# FLAT_LED.net
KiCad netlist of a schematic drawn in Altium Designer
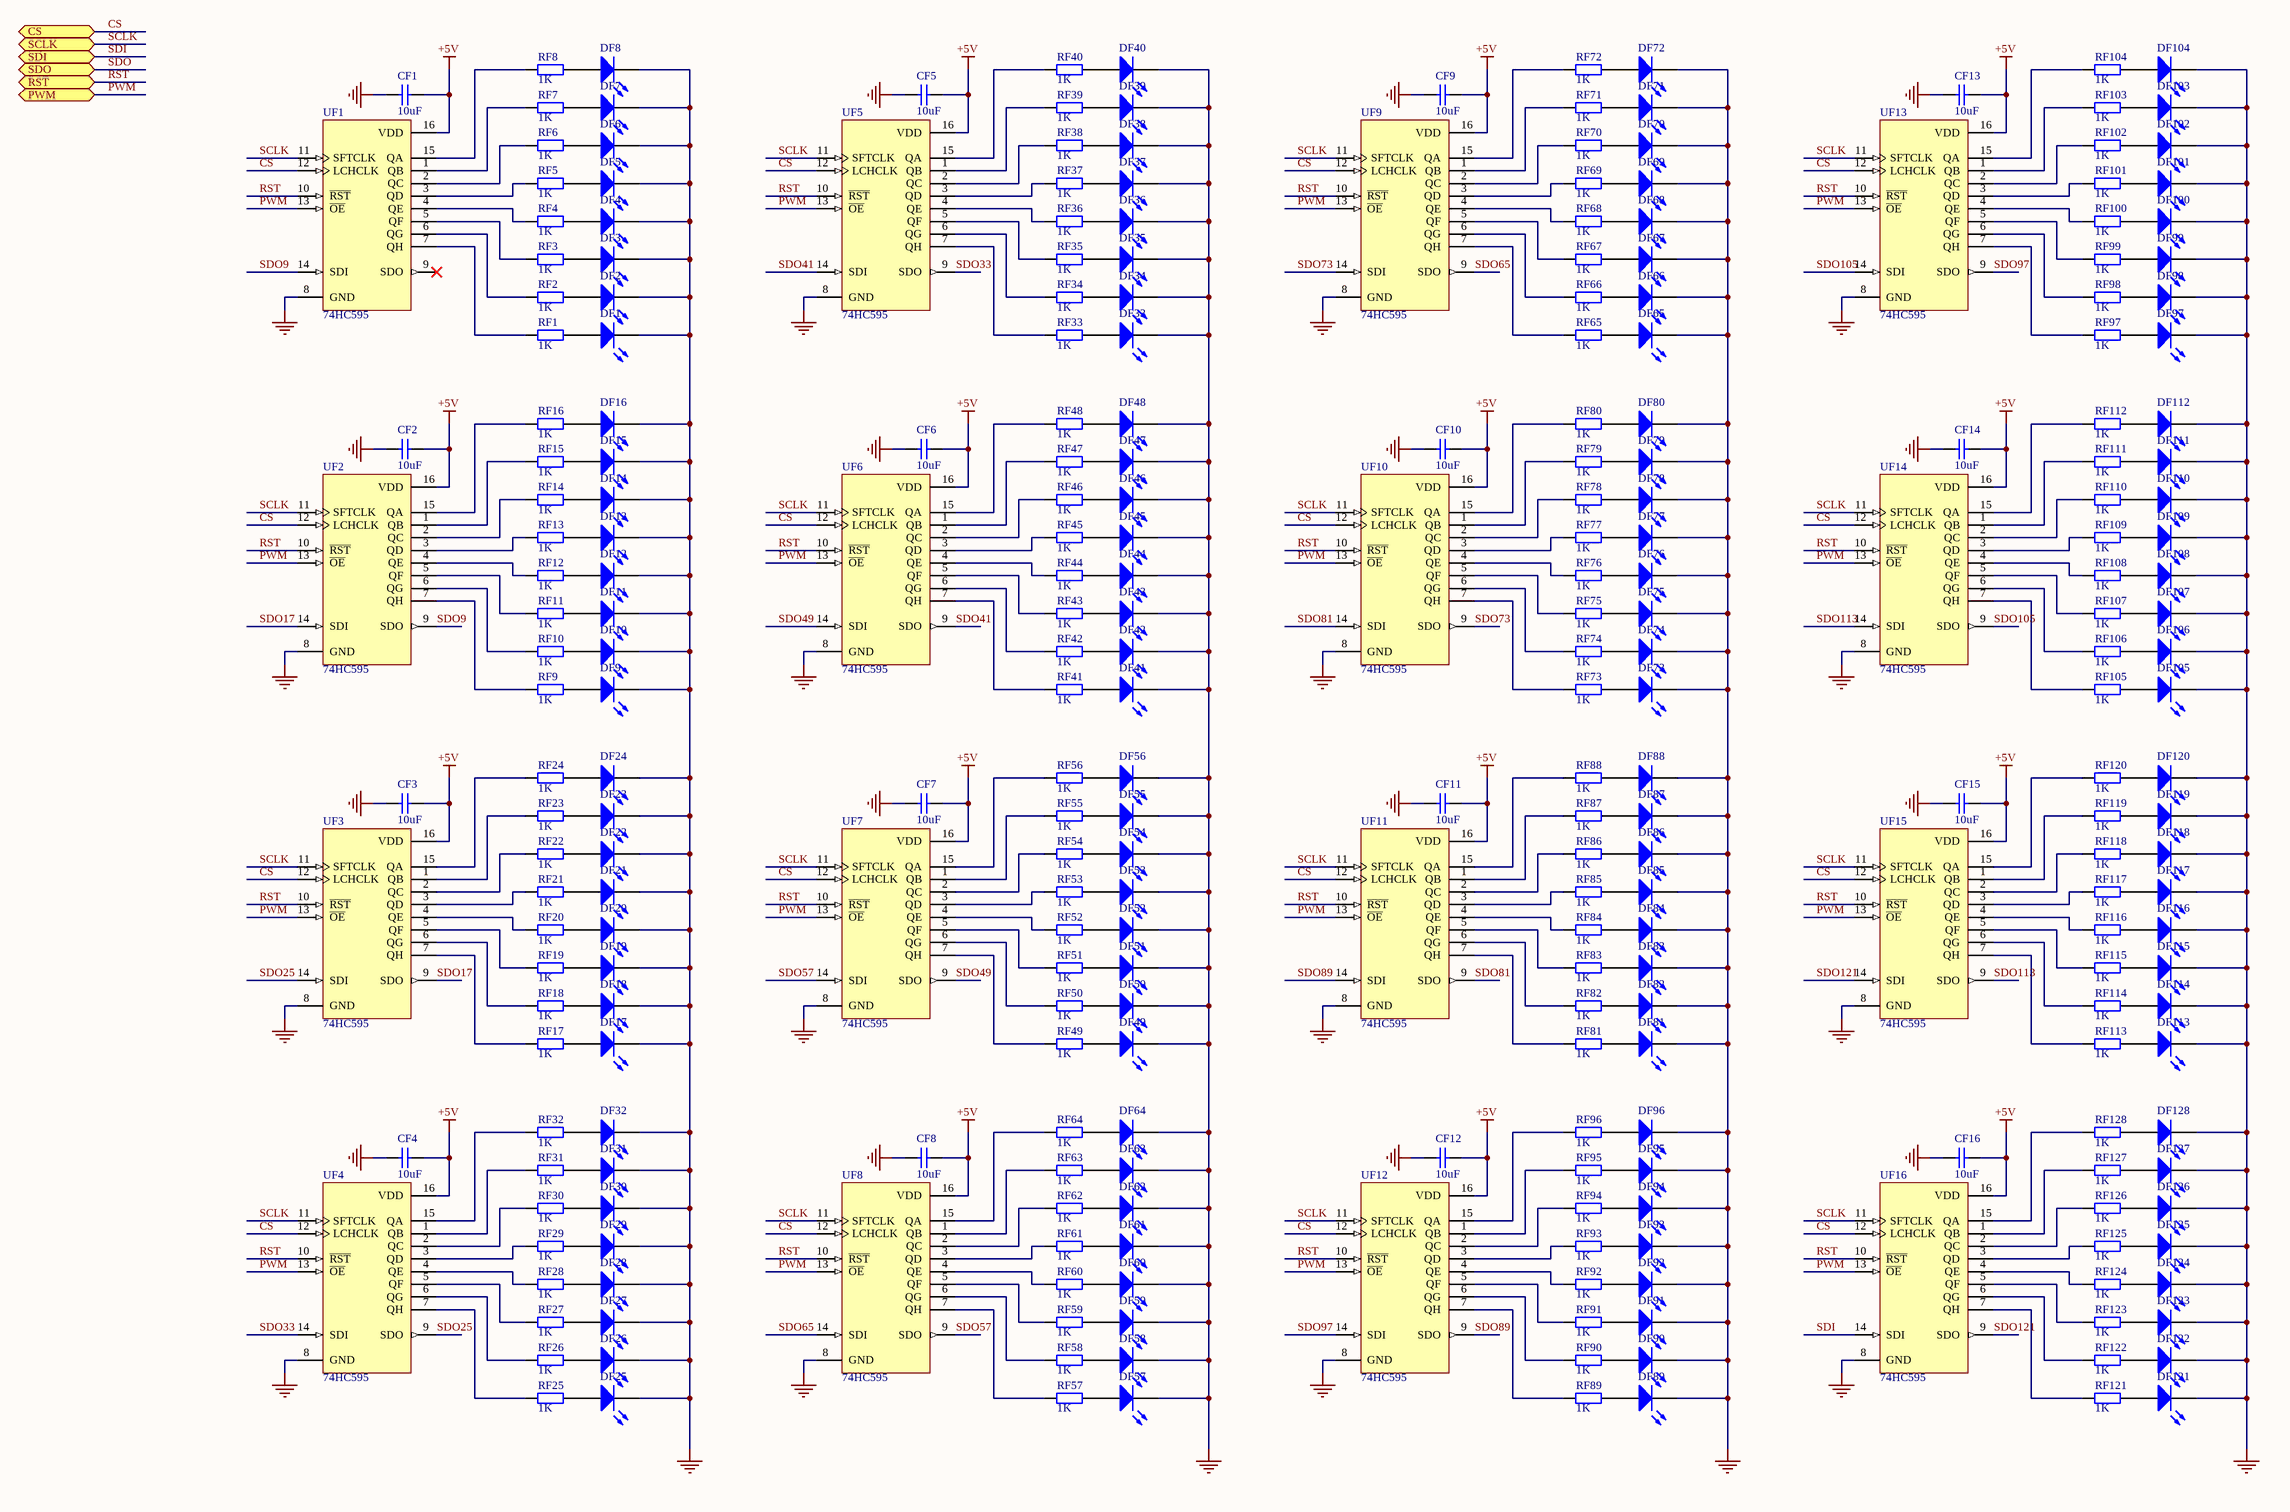
[diagram p0: FLAT_LED.SchDoc]

(export (version "E")
  (design (tool "Eeschema 10.0.6"))
  (components
    (comp (ref "CF1")
      (value "10uF")
      (footprint "CAPC1608N")
      (description "Capacitor")
      (fields (field (name "Comment") "Cap1") (field (name "PUBLISHER") "Altium Limited"))
      (libsource (lib "Peace的集成库") (part "Cap1"))
    )
    (comp (ref "CF2")
      (value "10uF")
      (footprint "CAPC1608N")
      (description "Capacitor")
      (fields (field (name "Comment") "Cap1") (field (name "PUBLISHER") "Altium Limited"))
      (libsource (lib "Peace的集成库") (part "Cap1"))
    )
    (comp (ref "CF3")
      (value "10uF")
      (footprint "CAPC1608N")
      (description "Capacitor")
      (fields (field (name "Comment") "Cap1") (field (name "PUBLISHER") "Altium Limited"))
      (libsource (lib "Peace的集成库") (part "Cap1"))
    )
    (comp (ref "CF4")
      (value "10uF")
      (footprint "CAPC1608N")
      (description "Capacitor")
      (fields (field (name "Comment") "Cap1") (field (name "PUBLISHER") "Altium Limited"))
      (libsource (lib "Peace的集成库") (part "Cap1"))
    )
    (comp (ref "CF5")
      (value "10uF")
      (footprint "CAPC1608N")
      (description "Capacitor")
      (fields (field (name "Comment") "Cap1") (field (name "PUBLISHER") "Altium Limited"))
      (libsource (lib "Peace的集成库") (part "Cap1"))
    )
    (comp (ref "CF6")
      (value "10uF")
      (footprint "CAPC1608N")
      (description "Capacitor")
      (fields (field (name "Comment") "Cap1") (field (name "PUBLISHER") "Altium Limited"))
      (libsource (lib "Peace的集成库") (part "Cap1"))
    )
    (comp (ref "CF7")
      (value "10uF")
      (footprint "CAPC1608N")
      (description "Capacitor")
      (fields (field (name "Comment") "Cap1") (field (name "PUBLISHER") "Altium Limited"))
      (libsource (lib "Peace的集成库") (part "Cap1"))
    )
    (comp (ref "CF8")
      (value "10uF")
      (footprint "CAPC1608N")
      (description "Capacitor")
      (fields (field (name "Comment") "Cap1") (field (name "PUBLISHER") "Altium Limited"))
      (libsource (lib "Peace的集成库") (part "Cap1"))
    )
    (comp (ref "CF9")
      (value "10uF")
      (footprint "CAPC1608N")
      (description "Capacitor")
      (fields (field (name "Comment") "Cap1") (field (name "PUBLISHER") "Altium Limited"))
      (libsource (lib "Peace的集成库") (part "Cap1"))
    )
    (comp (ref "CF10")
      (value "10uF")
      (footprint "CAPC1608N")
      (description "Capacitor")
      (fields (field (name "Comment") "Cap1") (field (name "PUBLISHER") "Altium Limited"))
      (libsource (lib "Peace的集成库") (part "Cap1"))
    )
    (comp (ref "CF11")
      (value "10uF")
      (footprint "CAPC1608N")
      (description "Capacitor")
      (fields (field (name "Comment") "Cap1") (field (name "PUBLISHER") "Altium Limited"))
      (libsource (lib "Peace的集成库") (part "Cap1"))
    )
    (comp (ref "CF12")
      (value "10uF")
      (footprint "CAPC1608N")
      (description "Capacitor")
      (fields (field (name "Comment") "Cap1") (field (name "PUBLISHER") "Altium Limited"))
      (libsource (lib "Peace的集成库") (part "Cap1"))
    )
    (comp (ref "CF13")
      (value "10uF")
      (footprint "CAPC1608N")
      (description "Capacitor")
      (fields (field (name "Comment") "Cap1") (field (name "PUBLISHER") "Altium Limited"))
      (libsource (lib "Peace的集成库") (part "Cap1"))
    )
    (comp (ref "CF14")
      (value "10uF")
      (footprint "CAPC1608N")
      (description "Capacitor")
      (fields (field (name "Comment") "Cap1") (field (name "PUBLISHER") "Altium Limited"))
      (libsource (lib "Peace的集成库") (part "Cap1"))
    )
    (comp (ref "CF15")
      (value "10uF")
      (footprint "CAPC1608N")
      (description "Capacitor")
      (fields (field (name "Comment") "Cap1") (field (name "PUBLISHER") "Altium Limited"))
      (libsource (lib "Peace的集成库") (part "Cap1"))
    )
    (comp (ref "CF16")
      (value "10uF")
      (footprint "CAPC1608N")
      (description "Capacitor")
      (fields (field (name "Comment") "Cap1") (field (name "PUBLISHER") "Altium Limited"))
      (libsource (lib "Peace的集成库") (part "Cap1"))
    )
    (comp (ref "DF1")
      (value "~")
      (footprint "CD1005-0402-L")
      (description "Typical RED, GREEN, YELLOW, AMBER GaAs LED")
      (fields (field (name "PUBLISHER") "Altium Limited"))
      (libsource (lib "Peace的集成库") (part "LED2"))
    )
    (comp (ref "DF2")
      (value "~")
      (footprint "CD1005-0402-L")
      (description "Typical RED, GREEN, YELLOW, AMBER GaAs LED")
      (fields (field (name "PUBLISHER") "Altium Limited"))
      (libsource (lib "Peace的集成库") (part "LED2"))
    )
    (comp (ref "DF3")
      (value "~")
      (footprint "CD1005-0402-L")
      (description "Typical RED, GREEN, YELLOW, AMBER GaAs LED")
      (fields (field (name "PUBLISHER") "Altium Limited"))
      (libsource (lib "Peace的集成库") (part "LED2"))
    )
    (comp (ref "DF4")
      (value "~")
      (footprint "CD1005-0402-L")
      (description "Typical RED, GREEN, YELLOW, AMBER GaAs LED")
      (fields (field (name "PUBLISHER") "Altium Limited"))
      (libsource (lib "Peace的集成库") (part "LED2"))
    )
    (comp (ref "DF5")
      (value "~")
      (footprint "CD1005-0402-L")
      (description "Typical RED, GREEN, YELLOW, AMBER GaAs LED")
      (fields (field (name "PUBLISHER") "Altium Limited"))
      (libsource (lib "Peace的集成库") (part "LED2"))
    )
    (comp (ref "DF6")
      (value "~")
      (footprint "CD1005-0402-L")
      (description "Typical RED, GREEN, YELLOW, AMBER GaAs LED")
      (fields (field (name "PUBLISHER") "Altium Limited"))
      (libsource (lib "Peace的集成库") (part "LED2"))
    )
    (comp (ref "DF7")
      (value "~")
      (footprint "CD1005-0402-L")
      (description "Typical RED, GREEN, YELLOW, AMBER GaAs LED")
      (fields (field (name "PUBLISHER") "Altium Limited"))
      (libsource (lib "Peace的集成库") (part "LED2"))
    )
    (comp (ref "DF8")
      (value "~")
      (footprint "CD1005-0402-L")
      (description "Typical RED, GREEN, YELLOW, AMBER GaAs LED")
      (fields (field (name "PUBLISHER") "Altium Limited"))
      (libsource (lib "Peace的集成库") (part "LED2"))
    )
    (comp (ref "DF9")
      (value "~")
      (footprint "CD1005-0402-L")
      (description "Typical RED, GREEN, YELLOW, AMBER GaAs LED")
      (fields (field (name "PUBLISHER") "Altium Limited"))
      (libsource (lib "Peace的集成库") (part "LED2"))
    )
    (comp (ref "DF10")
      (value "~")
      (footprint "CD1005-0402-L")
      (description "Typical RED, GREEN, YELLOW, AMBER GaAs LED")
      (fields (field (name "PUBLISHER") "Altium Limited"))
      (libsource (lib "Peace的集成库") (part "LED2"))
    )
    (comp (ref "DF11")
      (value "~")
      (footprint "CD1005-0402-L")
      (description "Typical RED, GREEN, YELLOW, AMBER GaAs LED")
      (fields (field (name "PUBLISHER") "Altium Limited"))
      (libsource (lib "Peace的集成库") (part "LED2"))
    )
    (comp (ref "DF12")
      (value "~")
      (footprint "CD1005-0402-L")
      (description "Typical RED, GREEN, YELLOW, AMBER GaAs LED")
      (fields (field (name "PUBLISHER") "Altium Limited"))
      (libsource (lib "Peace的集成库") (part "LED2"))
    )
    (comp (ref "DF13")
      (value "~")
      (footprint "CD1005-0402-L")
      (description "Typical RED, GREEN, YELLOW, AMBER GaAs LED")
      (fields (field (name "PUBLISHER") "Altium Limited"))
      (libsource (lib "Peace的集成库") (part "LED2"))
    )
    (comp (ref "DF14")
      (value "~")
      (footprint "CD1005-0402-L")
      (description "Typical RED, GREEN, YELLOW, AMBER GaAs LED")
      (fields (field (name "PUBLISHER") "Altium Limited"))
      (libsource (lib "Peace的集成库") (part "LED2"))
    )
    (comp (ref "DF15")
      (value "~")
      (footprint "CD1005-0402-L")
      (description "Typical RED, GREEN, YELLOW, AMBER GaAs LED")
      (fields (field (name "PUBLISHER") "Altium Limited"))
      (libsource (lib "Peace的集成库") (part "LED2"))
    )
    (comp (ref "DF16")
      (value "~")
      (footprint "CD1005-0402-L")
      (description "Typical RED, GREEN, YELLOW, AMBER GaAs LED")
      (fields (field (name "PUBLISHER") "Altium Limited"))
      (libsource (lib "Peace的集成库") (part "LED2"))
    )
    (comp (ref "DF17")
      (value "~")
      (footprint "CD1005-0402-L")
      (description "Typical RED, GREEN, YELLOW, AMBER GaAs LED")
      (fields (field (name "PUBLISHER") "Altium Limited"))
      (libsource (lib "Peace的集成库") (part "LED2"))
    )
    (comp (ref "DF18")
      (value "~")
      (footprint "CD1005-0402-L")
      (description "Typical RED, GREEN, YELLOW, AMBER GaAs LED")
      (fields (field (name "PUBLISHER") "Altium Limited"))
      (libsource (lib "Peace的集成库") (part "LED2"))
    )
    (comp (ref "DF19")
      (value "~")
      (footprint "CD1005-0402-L")
      (description "Typical RED, GREEN, YELLOW, AMBER GaAs LED")
      (fields (field (name "PUBLISHER") "Altium Limited"))
      (libsource (lib "Peace的集成库") (part "LED2"))
    )
    (comp (ref "DF20")
      (value "~")
      (footprint "CD1005-0402-L")
      (description "Typical RED, GREEN, YELLOW, AMBER GaAs LED")
      (fields (field (name "PUBLISHER") "Altium Limited"))
      (libsource (lib "Peace的集成库") (part "LED2"))
    )
    (comp (ref "DF21")
      (value "~")
      (footprint "CD1005-0402-L")
      (description "Typical RED, GREEN, YELLOW, AMBER GaAs LED")
      (fields (field (name "PUBLISHER") "Altium Limited"))
      (libsource (lib "Peace的集成库") (part "LED2"))
    )
    (comp (ref "DF22")
      (value "~")
      (footprint "CD1005-0402-L")
      (description "Typical RED, GREEN, YELLOW, AMBER GaAs LED")
      (fields (field (name "PUBLISHER") "Altium Limited"))
      (libsource (lib "Peace的集成库") (part "LED2"))
    )
    (comp (ref "DF23")
      (value "~")
      (footprint "CD1005-0402-L")
      (description "Typical RED, GREEN, YELLOW, AMBER GaAs LED")
      (fields (field (name "PUBLISHER") "Altium Limited"))
      (libsource (lib "Peace的集成库") (part "LED2"))
    )
    (comp (ref "DF24")
      (value "~")
      (footprint "CD1005-0402-L")
      (description "Typical RED, GREEN, YELLOW, AMBER GaAs LED")
      (fields (field (name "PUBLISHER") "Altium Limited"))
      (libsource (lib "Peace的集成库") (part "LED2"))
    )
    (comp (ref "DF25")
      (value "~")
      (footprint "CD1005-0402-L")
      (description "Typical RED, GREEN, YELLOW, AMBER GaAs LED")
      (fields (field (name "PUBLISHER") "Altium Limited"))
      (libsource (lib "Peace的集成库") (part "LED2"))
    )
    (comp (ref "DF26")
      (value "~")
      (footprint "CD1005-0402-L")
      (description "Typical RED, GREEN, YELLOW, AMBER GaAs LED")
      (fields (field (name "PUBLISHER") "Altium Limited"))
      (libsource (lib "Peace的集成库") (part "LED2"))
    )
    (comp (ref "DF27")
      (value "~")
      (footprint "CD1005-0402-L")
      (description "Typical RED, GREEN, YELLOW, AMBER GaAs LED")
      (fields (field (name "PUBLISHER") "Altium Limited"))
      (libsource (lib "Peace的集成库") (part "LED2"))
    )
    (comp (ref "DF28")
      (value "~")
      (footprint "CD1005-0402-L")
      (description "Typical RED, GREEN, YELLOW, AMBER GaAs LED")
      (fields (field (name "PUBLISHER") "Altium Limited"))
      (libsource (lib "Peace的集成库") (part "LED2"))
    )
    (comp (ref "DF29")
      (value "~")
      (footprint "CD1005-0402-L")
      (description "Typical RED, GREEN, YELLOW, AMBER GaAs LED")
      (fields (field (name "PUBLISHER") "Altium Limited"))
      (libsource (lib "Peace的集成库") (part "LED2"))
    )
    (comp (ref "DF30")
      (value "~")
      (footprint "CD1005-0402-L")
      (description "Typical RED, GREEN, YELLOW, AMBER GaAs LED")
      (fields (field (name "PUBLISHER") "Altium Limited"))
      (libsource (lib "Peace的集成库") (part "LED2"))
    )
    (comp (ref "DF31")
      (value "~")
      (footprint "CD1005-0402-L")
      (description "Typical RED, GREEN, YELLOW, AMBER GaAs LED")
      (fields (field (name "PUBLISHER") "Altium Limited"))
      (libsource (lib "Peace的集成库") (part "LED2"))
    )
    (comp (ref "DF32")
      (value "~")
      (footprint "CD1005-0402-L")
      (description "Typical RED, GREEN, YELLOW, AMBER GaAs LED")
      (fields (field (name "PUBLISHER") "Altium Limited"))
      (libsource (lib "Peace的集成库") (part "LED2"))
    )
    (comp (ref "DF33")
      (value "~")
      (footprint "CD1005-0402-L")
      (description "Typical RED, GREEN, YELLOW, AMBER GaAs LED")
      (fields (field (name "PUBLISHER") "Altium Limited"))
      (libsource (lib "Peace的集成库") (part "LED2"))
    )
    (comp (ref "DF34")
      (value "~")
      (footprint "CD1005-0402-L")
      (description "Typical RED, GREEN, YELLOW, AMBER GaAs LED")
      (fields (field (name "PUBLISHER") "Altium Limited"))
      (libsource (lib "Peace的集成库") (part "LED2"))
    )
    (comp (ref "DF35")
      (value "~")
      (footprint "CD1005-0402-L")
      (description "Typical RED, GREEN, YELLOW, AMBER GaAs LED")
      (fields (field (name "PUBLISHER") "Altium Limited"))
      (libsource (lib "Peace的集成库") (part "LED2"))
    )
    (comp (ref "DF36")
      (value "~")
      (footprint "CD1005-0402-L")
      (description "Typical RED, GREEN, YELLOW, AMBER GaAs LED")
      (fields (field (name "PUBLISHER") "Altium Limited"))
      (libsource (lib "Peace的集成库") (part "LED2"))
    )
    (comp (ref "DF37")
      (value "~")
      (footprint "CD1005-0402-L")
      (description "Typical RED, GREEN, YELLOW, AMBER GaAs LED")
      (fields (field (name "PUBLISHER") "Altium Limited"))
      (libsource (lib "Peace的集成库") (part "LED2"))
    )
    (comp (ref "DF38")
      (value "~")
      (footprint "CD1005-0402-L")
      (description "Typical RED, GREEN, YELLOW, AMBER GaAs LED")
      (fields (field (name "PUBLISHER") "Altium Limited"))
      (libsource (lib "Peace的集成库") (part "LED2"))
    )
    (comp (ref "DF39")
      (value "~")
      (footprint "CD1005-0402-L")
      (description "Typical RED, GREEN, YELLOW, AMBER GaAs LED")
      (fields (field (name "PUBLISHER") "Altium Limited"))
      (libsource (lib "Peace的集成库") (part "LED2"))
    )
    (comp (ref "DF40")
      (value "~")
      (footprint "CD1005-0402-L")
      (description "Typical RED, GREEN, YELLOW, AMBER GaAs LED")
      (fields (field (name "PUBLISHER") "Altium Limited"))
      (libsource (lib "Peace的集成库") (part "LED2"))
    )
    (comp (ref "DF41")
      (value "~")
      (footprint "CD1005-0402-L")
      (description "Typical RED, GREEN, YELLOW, AMBER GaAs LED")
      (fields (field (name "PUBLISHER") "Altium Limited"))
      (libsource (lib "Peace的集成库") (part "LED2"))
    )
    (comp (ref "DF42")
      (value "~")
      (footprint "CD1005-0402-L")
      (description "Typical RED, GREEN, YELLOW, AMBER GaAs LED")
      (fields (field (name "PUBLISHER") "Altium Limited"))
      (libsource (lib "Peace的集成库") (part "LED2"))
    )
    (comp (ref "DF43")
      (value "~")
      (footprint "CD1005-0402-L")
      (description "Typical RED, GREEN, YELLOW, AMBER GaAs LED")
      (fields (field (name "PUBLISHER") "Altium Limited"))
      (libsource (lib "Peace的集成库") (part "LED2"))
    )
    (comp (ref "DF44")
      (value "~")
      (footprint "CD1005-0402-L")
      (description "Typical RED, GREEN, YELLOW, AMBER GaAs LED")
      (fields (field (name "PUBLISHER") "Altium Limited"))
      (libsource (lib "Peace的集成库") (part "LED2"))
    )
    (comp (ref "DF45")
      (value "~")
      (footprint "CD1005-0402-L")
      (description "Typical RED, GREEN, YELLOW, AMBER GaAs LED")
      (fields (field (name "PUBLISHER") "Altium Limited"))
      (libsource (lib "Peace的集成库") (part "LED2"))
    )
    (comp (ref "DF46")
      (value "~")
      (footprint "CD1005-0402-L")
      (description "Typical RED, GREEN, YELLOW, AMBER GaAs LED")
      (fields (field (name "PUBLISHER") "Altium Limited"))
      (libsource (lib "Peace的集成库") (part "LED2"))
    )
    (comp (ref "DF47")
      (value "~")
      (footprint "CD1005-0402-L")
      (description "Typical RED, GREEN, YELLOW, AMBER GaAs LED")
      (fields (field (name "PUBLISHER") "Altium Limited"))
      (libsource (lib "Peace的集成库") (part "LED2"))
    )
    (comp (ref "DF48")
      (value "~")
      (footprint "CD1005-0402-L")
      (description "Typical RED, GREEN, YELLOW, AMBER GaAs LED")
      (fields (field (name "PUBLISHER") "Altium Limited"))
      (libsource (lib "Peace的集成库") (part "LED2"))
    )
    (comp (ref "DF49")
      (value "~")
      (footprint "CD1005-0402-L")
      (description "Typical RED, GREEN, YELLOW, AMBER GaAs LED")
      (fields (field (name "PUBLISHER") "Altium Limited"))
      (libsource (lib "Peace的集成库") (part "LED2"))
    )
    (comp (ref "DF50")
      (value "~")
      (footprint "CD1005-0402-L")
      (description "Typical RED, GREEN, YELLOW, AMBER GaAs LED")
      (fields (field (name "PUBLISHER") "Altium Limited"))
      (libsource (lib "Peace的集成库") (part "LED2"))
    )
    (comp (ref "DF51")
      (value "~")
      (footprint "CD1005-0402-L")
      (description "Typical RED, GREEN, YELLOW, AMBER GaAs LED")
      (fields (field (name "PUBLISHER") "Altium Limited"))
      (libsource (lib "Peace的集成库") (part "LED2"))
    )
    (comp (ref "DF52")
      (value "~")
      (footprint "CD1005-0402-L")
      (description "Typical RED, GREEN, YELLOW, AMBER GaAs LED")
      (fields (field (name "PUBLISHER") "Altium Limited"))
      (libsource (lib "Peace的集成库") (part "LED2"))
    )
    (comp (ref "DF53")
      (value "~")
      (footprint "CD1005-0402-L")
      (description "Typical RED, GREEN, YELLOW, AMBER GaAs LED")
      (fields (field (name "PUBLISHER") "Altium Limited"))
      (libsource (lib "Peace的集成库") (part "LED2"))
    )
    (comp (ref "DF54")
      (value "~")
      (footprint "CD1005-0402-L")
      (description "Typical RED, GREEN, YELLOW, AMBER GaAs LED")
      (fields (field (name "PUBLISHER") "Altium Limited"))
      (libsource (lib "Peace的集成库") (part "LED2"))
    )
    (comp (ref "DF55")
      (value "~")
      (footprint "CD1005-0402-L")
      (description "Typical RED, GREEN, YELLOW, AMBER GaAs LED")
      (fields (field (name "PUBLISHER") "Altium Limited"))
      (libsource (lib "Peace的集成库") (part "LED2"))
    )
    (comp (ref "DF56")
      (value "~")
      (footprint "CD1005-0402-L")
      (description "Typical RED, GREEN, YELLOW, AMBER GaAs LED")
      (fields (field (name "PUBLISHER") "Altium Limited"))
      (libsource (lib "Peace的集成库") (part "LED2"))
    )
    (comp (ref "DF57")
      (value "~")
      (footprint "CD1005-0402-L")
      (description "Typical RED, GREEN, YELLOW, AMBER GaAs LED")
      (fields (field (name "PUBLISHER") "Altium Limited"))
      (libsource (lib "Peace的集成库") (part "LED2"))
    )
    (comp (ref "DF58")
      (value "~")
      (footprint "CD1005-0402-L")
      (description "Typical RED, GREEN, YELLOW, AMBER GaAs LED")
      (fields (field (name "PUBLISHER") "Altium Limited"))
      (libsource (lib "Peace的集成库") (part "LED2"))
    )
    (comp (ref "DF59")
      (value "~")
      (footprint "CD1005-0402-L")
      (description "Typical RED, GREEN, YELLOW, AMBER GaAs LED")
      (fields (field (name "PUBLISHER") "Altium Limited"))
      (libsource (lib "Peace的集成库") (part "LED2"))
    )
    (comp (ref "DF60")
      (value "~")
      (footprint "CD1005-0402-L")
      (description "Typical RED, GREEN, YELLOW, AMBER GaAs LED")
      (fields (field (name "PUBLISHER") "Altium Limited"))
      (libsource (lib "Peace的集成库") (part "LED2"))
    )
    (comp (ref "DF61")
      (value "~")
      (footprint "CD1005-0402-L")
      (description "Typical RED, GREEN, YELLOW, AMBER GaAs LED")
      (fields (field (name "PUBLISHER") "Altium Limited"))
      (libsource (lib "Peace的集成库") (part "LED2"))
    )
    (comp (ref "DF62")
      (value "~")
      (footprint "CD1005-0402-L")
      (description "Typical RED, GREEN, YELLOW, AMBER GaAs LED")
      (fields (field (name "PUBLISHER") "Altium Limited"))
      (libsource (lib "Peace的集成库") (part "LED2"))
    )
    (comp (ref "DF63")
      (value "~")
      (footprint "CD1005-0402-L")
      (description "Typical RED, GREEN, YELLOW, AMBER GaAs LED")
      (fields (field (name "PUBLISHER") "Altium Limited"))
      (libsource (lib "Peace的集成库") (part "LED2"))
    )
    (comp (ref "DF64")
      (value "~")
      (footprint "CD1005-0402-L")
      (description "Typical RED, GREEN, YELLOW, AMBER GaAs LED")
      (fields (field (name "PUBLISHER") "Altium Limited"))
      (libsource (lib "Peace的集成库") (part "LED2"))
    )
    (comp (ref "DF65")
      (value "~")
      (footprint "CD1005-0402-L")
      (description "Typical RED, GREEN, YELLOW, AMBER GaAs LED")
      (fields (field (name "PUBLISHER") "Altium Limited"))
      (libsource (lib "Peace的集成库") (part "LED2"))
    )
    (comp (ref "DF66")
      (value "~")
      (footprint "CD1005-0402-L")
      (description "Typical RED, GREEN, YELLOW, AMBER GaAs LED")
      (fields (field (name "PUBLISHER") "Altium Limited"))
      (libsource (lib "Peace的集成库") (part "LED2"))
    )
    (comp (ref "DF67")
      (value "~")
      (footprint "CD1005-0402-L")
      (description "Typical RED, GREEN, YELLOW, AMBER GaAs LED")
      (fields (field (name "PUBLISHER") "Altium Limited"))
      (libsource (lib "Peace的集成库") (part "LED2"))
    )
    (comp (ref "DF68")
      (value "~")
      (footprint "CD1005-0402-L")
      (description "Typical RED, GREEN, YELLOW, AMBER GaAs LED")
      (fields (field (name "PUBLISHER") "Altium Limited"))
      (libsource (lib "Peace的集成库") (part "LED2"))
    )
    (comp (ref "DF69")
      (value "~")
      (footprint "CD1005-0402-L")
      (description "Typical RED, GREEN, YELLOW, AMBER GaAs LED")
      (fields (field (name "PUBLISHER") "Altium Limited"))
      (libsource (lib "Peace的集成库") (part "LED2"))
    )
    (comp (ref "DF70")
      (value "~")
      (footprint "CD1005-0402-L")
      (description "Typical RED, GREEN, YELLOW, AMBER GaAs LED")
      (fields (field (name "PUBLISHER") "Altium Limited"))
      (libsource (lib "Peace的集成库") (part "LED2"))
    )
    (comp (ref "DF71")
      (value "~")
      (footprint "CD1005-0402-L")
      (description "Typical RED, GREEN, YELLOW, AMBER GaAs LED")
      (fields (field (name "PUBLISHER") "Altium Limited"))
      (libsource (lib "Peace的集成库") (part "LED2"))
    )
    (comp (ref "DF72")
      (value "~")
      (footprint "CD1005-0402-L")
      (description "Typical RED, GREEN, YELLOW, AMBER GaAs LED")
      (fields (field (name "PUBLISHER") "Altium Limited"))
      (libsource (lib "Peace的集成库") (part "LED2"))
    )
    (comp (ref "DF73")
      (value "~")
      (footprint "CD1005-0402-L")
      (description "Typical RED, GREEN, YELLOW, AMBER GaAs LED")
      (fields (field (name "PUBLISHER") "Altium Limited"))
      (libsource (lib "Peace的集成库") (part "LED2"))
    )
    (comp (ref "DF74")
      (value "~")
      (footprint "CD1005-0402-L")
      (description "Typical RED, GREEN, YELLOW, AMBER GaAs LED")
      (fields (field (name "PUBLISHER") "Altium Limited"))
      (libsource (lib "Peace的集成库") (part "LED2"))
    )
    (comp (ref "DF75")
      (value "~")
      (footprint "CD1005-0402-L")
      (description "Typical RED, GREEN, YELLOW, AMBER GaAs LED")
      (fields (field (name "PUBLISHER") "Altium Limited"))
      (libsource (lib "Peace的集成库") (part "LED2"))
    )
    (comp (ref "DF76")
      (value "~")
      (footprint "CD1005-0402-L")
      (description "Typical RED, GREEN, YELLOW, AMBER GaAs LED")
      (fields (field (name "PUBLISHER") "Altium Limited"))
      (libsource (lib "Peace的集成库") (part "LED2"))
    )
    (comp (ref "DF77")
      (value "~")
      (footprint "CD1005-0402-L")
      (description "Typical RED, GREEN, YELLOW, AMBER GaAs LED")
      (fields (field (name "PUBLISHER") "Altium Limited"))
      (libsource (lib "Peace的集成库") (part "LED2"))
    )
    (comp (ref "DF78")
      (value "~")
      (footprint "CD1005-0402-L")
      (description "Typical RED, GREEN, YELLOW, AMBER GaAs LED")
      (fields (field (name "PUBLISHER") "Altium Limited"))
      (libsource (lib "Peace的集成库") (part "LED2"))
    )
    (comp (ref "DF79")
      (value "~")
      (footprint "CD1005-0402-L")
      (description "Typical RED, GREEN, YELLOW, AMBER GaAs LED")
      (fields (field (name "PUBLISHER") "Altium Limited"))
      (libsource (lib "Peace的集成库") (part "LED2"))
    )
    (comp (ref "DF80")
      (value "~")
      (footprint "CD1005-0402-L")
      (description "Typical RED, GREEN, YELLOW, AMBER GaAs LED")
      (fields (field (name "PUBLISHER") "Altium Limited"))
      (libsource (lib "Peace的集成库") (part "LED2"))
    )
    (comp (ref "DF81")
      (value "~")
      (footprint "CD1005-0402-L")
      (description "Typical RED, GREEN, YELLOW, AMBER GaAs LED")
      (fields (field (name "PUBLISHER") "Altium Limited"))
      (libsource (lib "Peace的集成库") (part "LED2"))
    )
    (comp (ref "DF82")
      (value "~")
      (footprint "CD1005-0402-L")
      (description "Typical RED, GREEN, YELLOW, AMBER GaAs LED")
      (fields (field (name "PUBLISHER") "Altium Limited"))
      (libsource (lib "Peace的集成库") (part "LED2"))
    )
    (comp (ref "DF83")
      (value "~")
      (footprint "CD1005-0402-L")
      (description "Typical RED, GREEN, YELLOW, AMBER GaAs LED")
      (fields (field (name "PUBLISHER") "Altium Limited"))
      (libsource (lib "Peace的集成库") (part "LED2"))
    )
    (comp (ref "DF84")
      (value "~")
      (footprint "CD1005-0402-L")
      (description "Typical RED, GREEN, YELLOW, AMBER GaAs LED")
      (fields (field (name "PUBLISHER") "Altium Limited"))
      (libsource (lib "Peace的集成库") (part "LED2"))
    )
    (comp (ref "DF85")
      (value "~")
      (footprint "CD1005-0402-L")
      (description "Typical RED, GREEN, YELLOW, AMBER GaAs LED")
      (fields (field (name "PUBLISHER") "Altium Limited"))
      (libsource (lib "Peace的集成库") (part "LED2"))
    )
    (comp (ref "DF86")
      (value "~")
      (footprint "CD1005-0402-L")
      (description "Typical RED, GREEN, YELLOW, AMBER GaAs LED")
      (fields (field (name "PUBLISHER") "Altium Limited"))
      (libsource (lib "Peace的集成库") (part "LED2"))
    )
    (comp (ref "DF87")
      (value "~")
      (footprint "CD1005-0402-L")
      (description "Typical RED, GREEN, YELLOW, AMBER GaAs LED")
      (fields (field (name "PUBLISHER") "Altium Limited"))
      (libsource (lib "Peace的集成库") (part "LED2"))
    )
    (comp (ref "DF88")
      (value "~")
      (footprint "CD1005-0402-L")
      (description "Typical RED, GREEN, YELLOW, AMBER GaAs LED")
      (fields (field (name "PUBLISHER") "Altium Limited"))
      (libsource (lib "Peace的集成库") (part "LED2"))
    )
    (comp (ref "DF89")
      (value "~")
      (footprint "CD1005-0402-L")
      (description "Typical RED, GREEN, YELLOW, AMBER GaAs LED")
      (fields (field (name "PUBLISHER") "Altium Limited"))
      (libsource (lib "Peace的集成库") (part "LED2"))
    )
    (comp (ref "DF90")
      (value "~")
      (footprint "CD1005-0402-L")
      (description "Typical RED, GREEN, YELLOW, AMBER GaAs LED")
      (fields (field (name "PUBLISHER") "Altium Limited"))
      (libsource (lib "Peace的集成库") (part "LED2"))
    )
    (comp (ref "DF91")
      (value "~")
      (footprint "CD1005-0402-L")
      (description "Typical RED, GREEN, YELLOW, AMBER GaAs LED")
      (fields (field (name "PUBLISHER") "Altium Limited"))
      (libsource (lib "Peace的集成库") (part "LED2"))
    )
    (comp (ref "DF92")
      (value "~")
      (footprint "CD1005-0402-L")
      (description "Typical RED, GREEN, YELLOW, AMBER GaAs LED")
      (fields (field (name "PUBLISHER") "Altium Limited"))
      (libsource (lib "Peace的集成库") (part "LED2"))
    )
    (comp (ref "DF93")
      (value "~")
      (footprint "CD1005-0402-L")
      (description "Typical RED, GREEN, YELLOW, AMBER GaAs LED")
      (fields (field (name "PUBLISHER") "Altium Limited"))
      (libsource (lib "Peace的集成库") (part "LED2"))
    )
    (comp (ref "DF94")
      (value "~")
      (footprint "CD1005-0402-L")
      (description "Typical RED, GREEN, YELLOW, AMBER GaAs LED")
      (fields (field (name "PUBLISHER") "Altium Limited"))
      (libsource (lib "Peace的集成库") (part "LED2"))
    )
    (comp (ref "DF95")
      (value "~")
      (footprint "CD1005-0402-L")
      (description "Typical RED, GREEN, YELLOW, AMBER GaAs LED")
      (fields (field (name "PUBLISHER") "Altium Limited"))
      (libsource (lib "Peace的集成库") (part "LED2"))
    )
    (comp (ref "DF96")
      (value "~")
      (footprint "CD1005-0402-L")
      (description "Typical RED, GREEN, YELLOW, AMBER GaAs LED")
      (fields (field (name "PUBLISHER") "Altium Limited"))
      (libsource (lib "Peace的集成库") (part "LED2"))
    )
    (comp (ref "DF97")
      (value "~")
      (footprint "CD1005-0402-L")
      (description "Typical RED, GREEN, YELLOW, AMBER GaAs LED")
      (fields (field (name "PUBLISHER") "Altium Limited"))
      (libsource (lib "Peace的集成库") (part "LED2"))
    )
    (comp (ref "DF98")
      (value "~")
      (footprint "CD1005-0402-L")
      (description "Typical RED, GREEN, YELLOW, AMBER GaAs LED")
      (fields (field (name "PUBLISHER") "Altium Limited"))
      (libsource (lib "Peace的集成库") (part "LED2"))
    )
    (comp (ref "DF99")
      (value "~")
      (footprint "CD1005-0402-L")
      (description "Typical RED, GREEN, YELLOW, AMBER GaAs LED")
      (fields (field (name "PUBLISHER") "Altium Limited"))
      (libsource (lib "Peace的集成库") (part "LED2"))
    )
    (comp (ref "DF100")
      (value "~")
      (footprint "CD1005-0402-L")
      (description "Typical RED, GREEN, YELLOW, AMBER GaAs LED")
      (fields (field (name "PUBLISHER") "Altium Limited"))
      (libsource (lib "Peace的集成库") (part "LED2"))
    )
    (comp (ref "DF101")
      (value "~")
      (footprint "CD1005-0402-L")
      (description "Typical RED, GREEN, YELLOW, AMBER GaAs LED")
      (fields (field (name "PUBLISHER") "Altium Limited"))
      (libsource (lib "Peace的集成库") (part "LED2"))
    )
    (comp (ref "DF102")
      (value "~")
      (footprint "CD1005-0402-L")
      (description "Typical RED, GREEN, YELLOW, AMBER GaAs LED")
      (fields (field (name "PUBLISHER") "Altium Limited"))
      (libsource (lib "Peace的集成库") (part "LED2"))
    )
    (comp (ref "DF103")
      (value "~")
      (footprint "CD1005-0402-L")
      (description "Typical RED, GREEN, YELLOW, AMBER GaAs LED")
      (fields (field (name "PUBLISHER") "Altium Limited"))
      (libsource (lib "Peace的集成库") (part "LED2"))
    )
    (comp (ref "DF104")
      (value "~")
      (footprint "CD1005-0402-L")
      (description "Typical RED, GREEN, YELLOW, AMBER GaAs LED")
      (fields (field (name "PUBLISHER") "Altium Limited"))
      (libsource (lib "Peace的集成库") (part "LED2"))
    )
    (comp (ref "DF105")
      (value "~")
      (footprint "CD1005-0402-L")
      (description "Typical RED, GREEN, YELLOW, AMBER GaAs LED")
      (fields (field (name "PUBLISHER") "Altium Limited"))
      (libsource (lib "Peace的集成库") (part "LED2"))
    )
    (comp (ref "DF106")
      (value "~")
      (footprint "CD1005-0402-L")
      (description "Typical RED, GREEN, YELLOW, AMBER GaAs LED")
      (fields (field (name "PUBLISHER") "Altium Limited"))
      (libsource (lib "Peace的集成库") (part "LED2"))
    )
    (comp (ref "DF107")
      (value "~")
      (footprint "CD1005-0402-L")
      (description "Typical RED, GREEN, YELLOW, AMBER GaAs LED")
      (fields (field (name "PUBLISHER") "Altium Limited"))
      (libsource (lib "Peace的集成库") (part "LED2"))
    )
    (comp (ref "DF108")
      (value "~")
      (footprint "CD1005-0402-L")
      (description "Typical RED, GREEN, YELLOW, AMBER GaAs LED")
      (fields (field (name "PUBLISHER") "Altium Limited"))
      (libsource (lib "Peace的集成库") (part "LED2"))
    )
    (comp (ref "DF109")
      (value "~")
      (footprint "CD1005-0402-L")
      (description "Typical RED, GREEN, YELLOW, AMBER GaAs LED")
      (fields (field (name "PUBLISHER") "Altium Limited"))
      (libsource (lib "Peace的集成库") (part "LED2"))
    )
    (comp (ref "DF110")
      (value "~")
      (footprint "CD1005-0402-L")
      (description "Typical RED, GREEN, YELLOW, AMBER GaAs LED")
      (fields (field (name "PUBLISHER") "Altium Limited"))
      (libsource (lib "Peace的集成库") (part "LED2"))
    )
    (comp (ref "DF111")
      (value "~")
      (footprint "CD1005-0402-L")
      (description "Typical RED, GREEN, YELLOW, AMBER GaAs LED")
      (fields (field (name "PUBLISHER") "Altium Limited"))
      (libsource (lib "Peace的集成库") (part "LED2"))
    )
    (comp (ref "DF112")
      (value "~")
      (footprint "CD1005-0402-L")
      (description "Typical RED, GREEN, YELLOW, AMBER GaAs LED")
      (fields (field (name "PUBLISHER") "Altium Limited"))
      (libsource (lib "Peace的集成库") (part "LED2"))
    )
    (comp (ref "DF113")
      (value "~")
      (footprint "CD1005-0402-L")
      (description "Typical RED, GREEN, YELLOW, AMBER GaAs LED")
      (fields (field (name "PUBLISHER") "Altium Limited"))
      (libsource (lib "Peace的集成库") (part "LED2"))
    )
    (comp (ref "DF114")
      (value "~")
      (footprint "CD1005-0402-L")
      (description "Typical RED, GREEN, YELLOW, AMBER GaAs LED")
      (fields (field (name "PUBLISHER") "Altium Limited"))
      (libsource (lib "Peace的集成库") (part "LED2"))
    )
    (comp (ref "DF115")
      (value "~")
      (footprint "CD1005-0402-L")
      (description "Typical RED, GREEN, YELLOW, AMBER GaAs LED")
      (fields (field (name "PUBLISHER") "Altium Limited"))
      (libsource (lib "Peace的集成库") (part "LED2"))
    )
    (comp (ref "DF116")
      (value "~")
      (footprint "CD1005-0402-L")
      (description "Typical RED, GREEN, YELLOW, AMBER GaAs LED")
      (fields (field (name "PUBLISHER") "Altium Limited"))
      (libsource (lib "Peace的集成库") (part "LED2"))
    )
    (comp (ref "DF117")
      (value "~")
      (footprint "CD1005-0402-L")
      (description "Typical RED, GREEN, YELLOW, AMBER GaAs LED")
      (fields (field (name "PUBLISHER") "Altium Limited"))
      (libsource (lib "Peace的集成库") (part "LED2"))
    )
    (comp (ref "DF118")
      (value "~")
      (footprint "CD1005-0402-L")
      (description "Typical RED, GREEN, YELLOW, AMBER GaAs LED")
      (fields (field (name "PUBLISHER") "Altium Limited"))
      (libsource (lib "Peace的集成库") (part "LED2"))
    )
    (comp (ref "DF119")
      (value "~")
      (footprint "CD1005-0402-L")
      (description "Typical RED, GREEN, YELLOW, AMBER GaAs LED")
      (fields (field (name "PUBLISHER") "Altium Limited"))
      (libsource (lib "Peace的集成库") (part "LED2"))
    )
    (comp (ref "DF120")
      (value "~")
      (footprint "CD1005-0402-L")
      (description "Typical RED, GREEN, YELLOW, AMBER GaAs LED")
      (fields (field (name "PUBLISHER") "Altium Limited"))
      (libsource (lib "Peace的集成库") (part "LED2"))
    )
    (comp (ref "DF121")
      (value "~")
      (footprint "CD1005-0402-L")
      (description "Typical RED, GREEN, YELLOW, AMBER GaAs LED")
      (fields (field (name "PUBLISHER") "Altium Limited"))
      (libsource (lib "Peace的集成库") (part "LED2"))
    )
    (comp (ref "DF122")
      (value "~")
      (footprint "CD1005-0402-L")
      (description "Typical RED, GREEN, YELLOW, AMBER GaAs LED")
      (fields (field (name "PUBLISHER") "Altium Limited"))
      (libsource (lib "Peace的集成库") (part "LED2"))
    )
    (comp (ref "DF123")
      (value "~")
      (footprint "CD1005-0402-L")
      (description "Typical RED, GREEN, YELLOW, AMBER GaAs LED")
      (fields (field (name "PUBLISHER") "Altium Limited"))
      (libsource (lib "Peace的集成库") (part "LED2"))
    )
    (comp (ref "DF124")
      (value "~")
      (footprint "CD1005-0402-L")
      (description "Typical RED, GREEN, YELLOW, AMBER GaAs LED")
      (fields (field (name "PUBLISHER") "Altium Limited"))
      (libsource (lib "Peace的集成库") (part "LED2"))
    )
    (comp (ref "DF125")
      (value "~")
      (footprint "CD1005-0402-L")
      (description "Typical RED, GREEN, YELLOW, AMBER GaAs LED")
      (fields (field (name "PUBLISHER") "Altium Limited"))
      (libsource (lib "Peace的集成库") (part "LED2"))
    )
    (comp (ref "DF126")
      (value "~")
      (footprint "CD1005-0402-L")
      (description "Typical RED, GREEN, YELLOW, AMBER GaAs LED")
      (fields (field (name "PUBLISHER") "Altium Limited"))
      (libsource (lib "Peace的集成库") (part "LED2"))
    )
    (comp (ref "DF127")
      (value "~")
      (footprint "CD1005-0402-L")
      (description "Typical RED, GREEN, YELLOW, AMBER GaAs LED")
      (fields (field (name "PUBLISHER") "Altium Limited"))
      (libsource (lib "Peace的集成库") (part "LED2"))
    )
    (comp (ref "DF128")
      (value "~")
      (footprint "CD1005-0402-L")
      (description "Typical RED, GREEN, YELLOW, AMBER GaAs LED")
      (fields (field (name "PUBLISHER") "Altium Limited"))
      (libsource (lib "Peace的集成库") (part "LED2"))
    )
    (comp (ref "RF1")
      (value "1K")
      (footprint "RESC1005L-0.5")
      (description "Resistor")
      (fields (field (name "Comment") "Res1") (field (name "PUBLISHER") "Altium Limited"))
      (libsource (lib "Peace的集成库") (part "Res1"))
    )
    (comp (ref "RF2")
      (value "1K")
      (footprint "RESC1005L-0.5")
      (description "Resistor")
      (fields (field (name "Comment") "Res1") (field (name "PUBLISHER") "Altium Limited"))
      (libsource (lib "Peace的集成库") (part "Res1"))
    )
    (comp (ref "RF3")
      (value "1K")
      (footprint "RESC1005L-0.5")
      (description "Resistor")
      (fields (field (name "Comment") "Res1") (field (name "PUBLISHER") "Altium Limited"))
      (libsource (lib "Peace的集成库") (part "Res1"))
    )
    (comp (ref "RF4")
      (value "1K")
      (footprint "RESC1005L-0.5")
      (description "Resistor")
      (fields (field (name "Comment") "Res1") (field (name "PUBLISHER") "Altium Limited"))
      (libsource (lib "Peace的集成库") (part "Res1"))
    )
    (comp (ref "RF5")
      (value "1K")
      (footprint "RESC1005L-0.5")
      (description "Resistor")
      (fields (field (name "Comment") "Res1") (field (name "PUBLISHER") "Altium Limited"))
      (libsource (lib "Peace的集成库") (part "Res1"))
    )
    (comp (ref "RF6")
      (value "1K")
      (footprint "RESC1005L-0.5")
      (description "Resistor")
      (fields (field (name "Comment") "Res1") (field (name "PUBLISHER") "Altium Limited"))
      (libsource (lib "Peace的集成库") (part "Res1"))
    )
    (comp (ref "RF7")
      (value "1K")
      (footprint "RESC1005L-0.5")
      (description "Resistor")
      (fields (field (name "Comment") "Res1") (field (name "PUBLISHER") "Altium Limited"))
      (libsource (lib "Peace的集成库") (part "Res1"))
    )
    (comp (ref "RF8")
      (value "1K")
      (footprint "RESC1005L-0.5")
      (description "Resistor")
      (fields (field (name "Comment") "Res1") (field (name "PUBLISHER") "Altium Limited"))
      (libsource (lib "Peace的集成库") (part "Res1"))
    )
    (comp (ref "RF9")
      (value "1K")
      (footprint "RESC1005L-0.5")
      (description "Resistor")
      (fields (field (name "Comment") "Res1") (field (name "PUBLISHER") "Altium Limited"))
      (libsource (lib "Peace的集成库") (part "Res1"))
    )
    (comp (ref "RF10")
      (value "1K")
      (footprint "RESC1005L-0.5")
      (description "Resistor")
      (fields (field (name "Comment") "Res1") (field (name "PUBLISHER") "Altium Limited"))
      (libsource (lib "Peace的集成库") (part "Res1"))
    )
    (comp (ref "RF11")
      (value "1K")
      (footprint "RESC1005L-0.5")
      (description "Resistor")
      (fields (field (name "Comment") "Res1") (field (name "PUBLISHER") "Altium Limited"))
      (libsource (lib "Peace的集成库") (part "Res1"))
    )
    (comp (ref "RF12")
      (value "1K")
      (footprint "RESC1005L-0.5")
      (description "Resistor")
      (fields (field (name "Comment") "Res1") (field (name "PUBLISHER") "Altium Limited"))
      (libsource (lib "Peace的集成库") (part "Res1"))
    )
    (comp (ref "RF13")
      (value "1K")
      (footprint "RESC1005L-0.5")
      (description "Resistor")
      (fields (field (name "Comment") "Res1") (field (name "PUBLISHER") "Altium Limited"))
      (libsource (lib "Peace的集成库") (part "Res1"))
    )
    (comp (ref "RF14")
      (value "1K")
      (footprint "RESC1005L-0.5")
      (description "Resistor")
      (fields (field (name "Comment") "Res1") (field (name "PUBLISHER") "Altium Limited"))
      (libsource (lib "Peace的集成库") (part "Res1"))
    )
    (comp (ref "RF15")
      (value "1K")
      (footprint "RESC1005L-0.5")
      (description "Resistor")
      (fields (field (name "Comment") "Res1") (field (name "PUBLISHER") "Altium Limited"))
      (libsource (lib "Peace的集成库") (part "Res1"))
    )
    (comp (ref "RF16")
      (value "1K")
      (footprint "RESC1005L-0.5")
      (description "Resistor")
      (fields (field (name "Comment") "Res1") (field (name "PUBLISHER") "Altium Limited"))
      (libsource (lib "Peace的集成库") (part "Res1"))
    )
    (comp (ref "RF17")
      (value "1K")
      (footprint "RESC1005L-0.5")
      (description "Resistor")
      (fields (field (name "Comment") "Res1") (field (name "PUBLISHER") "Altium Limited"))
      (libsource (lib "Peace的集成库") (part "Res1"))
    )
    (comp (ref "RF18")
      (value "1K")
      (footprint "RESC1005L-0.5")
      (description "Resistor")
      (fields (field (name "Comment") "Res1") (field (name "PUBLISHER") "Altium Limited"))
      (libsource (lib "Peace的集成库") (part "Res1"))
    )
    (comp (ref "RF19")
      (value "1K")
      (footprint "RESC1005L-0.5")
      (description "Resistor")
      (fields (field (name "Comment") "Res1") (field (name "PUBLISHER") "Altium Limited"))
      (libsource (lib "Peace的集成库") (part "Res1"))
    )
    (comp (ref "RF20")
      (value "1K")
      (footprint "RESC1005L-0.5")
      (description "Resistor")
      (fields (field (name "Comment") "Res1") (field (name "PUBLISHER") "Altium Limited"))
      (libsource (lib "Peace的集成库") (part "Res1"))
    )
    (comp (ref "RF21")
      (value "1K")
      (footprint "RESC1005L-0.5")
      (description "Resistor")
      (fields (field (name "Comment") "Res1") (field (name "PUBLISHER") "Altium Limited"))
      (libsource (lib "Peace的集成库") (part "Res1"))
    )
    (comp (ref "RF22")
      (value "1K")
      (footprint "RESC1005L-0.5")
      (description "Resistor")
      (fields (field (name "Comment") "Res1") (field (name "PUBLISHER") "Altium Limited"))
      (libsource (lib "Peace的集成库") (part "Res1"))
    )
    (comp (ref "RF23")
      (value "1K")
      (footprint "RESC1005L-0.5")
      (description "Resistor")
      (fields (field (name "Comment") "Res1") (field (name "PUBLISHER") "Altium Limited"))
      (libsource (lib "Peace的集成库") (part "Res1"))
    )
    (comp (ref "RF24")
      (value "1K")
      (footprint "RESC1005L-0.5")
      (description "Resistor")
      (fields (field (name "Comment") "Res1") (field (name "PUBLISHER") "Altium Limited"))
      (libsource (lib "Peace的集成库") (part "Res1"))
    )
    (comp (ref "RF25")
      (value "1K")
      (footprint "RESC1005L-0.5")
      (description "Resistor")
      (fields (field (name "Comment") "Res1") (field (name "PUBLISHER") "Altium Limited"))
      (libsource (lib "Peace的集成库") (part "Res1"))
    )
    (comp (ref "RF26")
      (value "1K")
      (footprint "RESC1005L-0.5")
      (description "Resistor")
      (fields (field (name "Comment") "Res1") (field (name "PUBLISHER") "Altium Limited"))
      (libsource (lib "Peace的集成库") (part "Res1"))
    )
    (comp (ref "RF27")
      (value "1K")
      (footprint "RESC1005L-0.5")
      (description "Resistor")
      (fields (field (name "Comment") "Res1") (field (name "PUBLISHER") "Altium Limited"))
      (libsource (lib "Peace的集成库") (part "Res1"))
    )
    (comp (ref "RF28")
      (value "1K")
      (footprint "RESC1005L-0.5")
      (description "Resistor")
      (fields (field (name "Comment") "Res1") (field (name "PUBLISHER") "Altium Limited"))
      (libsource (lib "Peace的集成库") (part "Res1"))
    )
    (comp (ref "RF29")
      (value "1K")
      (footprint "RESC1005L-0.5")
      (description "Resistor")
      (fields (field (name "Comment") "Res1") (field (name "PUBLISHER") "Altium Limited"))
      (libsource (lib "Peace的集成库") (part "Res1"))
    )
    (comp (ref "RF30")
      (value "1K")
      (footprint "RESC1005L-0.5")
      (description "Resistor")
      (fields (field (name "Comment") "Res1") (field (name "PUBLISHER") "Altium Limited"))
      (libsource (lib "Peace的集成库") (part "Res1"))
    )
    (comp (ref "RF31")
      (value "1K")
      (footprint "RESC1005L-0.5")
      (description "Resistor")
      (fields (field (name "Comment") "Res1") (field (name "PUBLISHER") "Altium Limited"))
      (libsource (lib "Peace的集成库") (part "Res1"))
    )
    (comp (ref "RF32")
      (value "1K")
      (footprint "RESC1005L-0.5")
      (description "Resistor")
      (fields (field (name "Comment") "Res1") (field (name "PUBLISHER") "Altium Limited"))
      (libsource (lib "Peace的集成库") (part "Res1"))
    )
    (comp (ref "RF33")
      (value "1K")
      (footprint "RESC1005L-0.5")
      (description "Resistor")
      (fields (field (name "Comment") "Res1") (field (name "PUBLISHER") "Altium Limited"))
      (libsource (lib "Peace的集成库") (part "Res1"))
    )
    (comp (ref "RF34")
      (value "1K")
      (footprint "RESC1005L-0.5")
      (description "Resistor")
      (fields (field (name "Comment") "Res1") (field (name "PUBLISHER") "Altium Limited"))
      (libsource (lib "Peace的集成库") (part "Res1"))
    )
    (comp (ref "RF35")
      (value "1K")
      (footprint "RESC1005L-0.5")
      (description "Resistor")
      (fields (field (name "Comment") "Res1") (field (name "PUBLISHER") "Altium Limited"))
      (libsource (lib "Peace的集成库") (part "Res1"))
    )
    (comp (ref "RF36")
      (value "1K")
      (footprint "RESC1005L-0.5")
      (description "Resistor")
      (fields (field (name "Comment") "Res1") (field (name "PUBLISHER") "Altium Limited"))
      (libsource (lib "Peace的集成库") (part "Res1"))
    )
    (comp (ref "RF37")
      (value "1K")
      (footprint "RESC1005L-0.5")
      (description "Resistor")
      (fields (field (name "Comment") "Res1") (field (name "PUBLISHER") "Altium Limited"))
      (libsource (lib "Peace的集成库") (part "Res1"))
    )
    (comp (ref "RF38")
      (value "1K")
      (footprint "RESC1005L-0.5")
      (description "Resistor")
      (fields (field (name "Comment") "Res1") (field (name "PUBLISHER") "Altium Limited"))
      (libsource (lib "Peace的集成库") (part "Res1"))
    )
    (comp (ref "RF39")
      (value "1K")
      (footprint "RESC1005L-0.5")
      (description "Resistor")
      (fields (field (name "Comment") "Res1") (field (name "PUBLISHER") "Altium Limited"))
      (libsource (lib "Peace的集成库") (part "Res1"))
    )
    (comp (ref "RF40")
      (value "1K")
      (footprint "RESC1005L-0.5")
      (description "Resistor")
      (fields (field (name "Comment") "Res1") (field (name "PUBLISHER") "Altium Limited"))
      (libsource (lib "Peace的集成库") (part "Res1"))
    )
    (comp (ref "RF41")
      (value "1K")
      (footprint "RESC1005L-0.5")
      (description "Resistor")
      (fields (field (name "Comment") "Res1") (field (name "PUBLISHER") "Altium Limited"))
      (libsource (lib "Peace的集成库") (part "Res1"))
    )
    (comp (ref "RF42")
      (value "1K")
      (footprint "RESC1005L-0.5")
      (description "Resistor")
      (fields (field (name "Comment") "Res1") (field (name "PUBLISHER") "Altium Limited"))
      (libsource (lib "Peace的集成库") (part "Res1"))
    )
    (comp (ref "RF43")
      (value "1K")
      (footprint "RESC1005L-0.5")
      (description "Resistor")
      (fields (field (name "Comment") "Res1") (field (name "PUBLISHER") "Altium Limited"))
      (libsource (lib "Peace的集成库") (part "Res1"))
    )
    (comp (ref "RF44")
      (value "1K")
      (footprint "RESC1005L-0.5")
      (description "Resistor")
      (fields (field (name "Comment") "Res1") (field (name "PUBLISHER") "Altium Limited"))
      (libsource (lib "Peace的集成库") (part "Res1"))
    )
    (comp (ref "RF45")
      (value "1K")
      (footprint "RESC1005L-0.5")
      (description "Resistor")
      (fields (field (name "Comment") "Res1") (field (name "PUBLISHER") "Altium Limited"))
      (libsource (lib "Peace的集成库") (part "Res1"))
    )
    (comp (ref "RF46")
      (value "1K")
      (footprint "RESC1005L-0.5")
      (description "Resistor")
      (fields (field (name "Comment") "Res1") (field (name "PUBLISHER") "Altium Limited"))
      (libsource (lib "Peace的集成库") (part "Res1"))
    )
    (comp (ref "RF47")
      (value "1K")
      (footprint "RESC1005L-0.5")
      (description "Resistor")
      (fields (field (name "Comment") "Res1") (field (name "PUBLISHER") "Altium Limited"))
      (libsource (lib "Peace的集成库") (part "Res1"))
    )
    (comp (ref "RF48")
      (value "1K")
      (footprint "RESC1005L-0.5")
      (description "Resistor")
      (fields (field (name "Comment") "Res1") (field (name "PUBLISHER") "Altium Limited"))
      (libsource (lib "Peace的集成库") (part "Res1"))
    )
    (comp (ref "RF49")
      (value "1K")
      (footprint "RESC1005L-0.5")
      (description "Resistor")
      (fields (field (name "Comment") "Res1") (field (name "PUBLISHER") "Altium Limited"))
      (libsource (lib "Peace的集成库") (part "Res1"))
    )
    (comp (ref "RF50")
      (value "1K")
      (footprint "RESC1005L-0.5")
      (description "Resistor")
      (fields (field (name "Comment") "Res1") (field (name "PUBLISHER") "Altium Limited"))
      (libsource (lib "Peace的集成库") (part "Res1"))
    )
    (comp (ref "RF51")
      (value "1K")
      (footprint "RESC1005L-0.5")
      (description "Resistor")
      (fields (field (name "Comment") "Res1") (field (name "PUBLISHER") "Altium Limited"))
      (libsource (lib "Peace的集成库") (part "Res1"))
    )
    (comp (ref "RF52")
      (value "1K")
      (footprint "RESC1005L-0.5")
      (description "Resistor")
      (fields (field (name "Comment") "Res1") (field (name "PUBLISHER") "Altium Limited"))
      (libsource (lib "Peace的集成库") (part "Res1"))
    )
    (comp (ref "RF53")
      (value "1K")
      (footprint "RESC1005L-0.5")
      (description "Resistor")
      (fields (field (name "Comment") "Res1") (field (name "PUBLISHER") "Altium Limited"))
      (libsource (lib "Peace的集成库") (part "Res1"))
    )
    (comp (ref "RF54")
      (value "1K")
      (footprint "RESC1005L-0.5")
      (description "Resistor")
      (fields (field (name "Comment") "Res1") (field (name "PUBLISHER") "Altium Limited"))
      (libsource (lib "Peace的集成库") (part "Res1"))
    )
    (comp (ref "RF55")
      (value "1K")
      (footprint "RESC1005L-0.5")
      (description "Resistor")
      (fields (field (name "Comment") "Res1") (field (name "PUBLISHER") "Altium Limited"))
      (libsource (lib "Peace的集成库") (part "Res1"))
    )
    (comp (ref "RF56")
      (value "1K")
      (footprint "RESC1005L-0.5")
      (description "Resistor")
      (fields (field (name "Comment") "Res1") (field (name "PUBLISHER") "Altium Limited"))
      (libsource (lib "Peace的集成库") (part "Res1"))
    )
    (comp (ref "RF57")
      (value "1K")
      (footprint "RESC1005L-0.5")
      (description "Resistor")
      (fields (field (name "Comment") "Res1") (field (name "PUBLISHER") "Altium Limited"))
      (libsource (lib "Peace的集成库") (part "Res1"))
    )
    (comp (ref "RF58")
      (value "1K")
      (footprint "RESC1005L-0.5")
      (description "Resistor")
      (fields (field (name "Comment") "Res1") (field (name "PUBLISHER") "Altium Limited"))
      (libsource (lib "Peace的集成库") (part "Res1"))
    )
    (comp (ref "RF59")
      (value "1K")
      (footprint "RESC1005L-0.5")
      (description "Resistor")
      (fields (field (name "Comment") "Res1") (field (name "PUBLISHER") "Altium Limited"))
      (libsource (lib "Peace的集成库") (part "Res1"))
    )
    (comp (ref "RF60")
      (value "1K")
      (footprint "RESC1005L-0.5")
      (description "Resistor")
      (fields (field (name "Comment") "Res1") (field (name "PUBLISHER") "Altium Limited"))
      (libsource (lib "Peace的集成库") (part "Res1"))
    )
    (comp (ref "RF61")
      (value "1K")
      (footprint "RESC1005L-0.5")
      (description "Resistor")
      (fields (field (name "Comment") "Res1") (field (name "PUBLISHER") "Altium Limited"))
      (libsource (lib "Peace的集成库") (part "Res1"))
    )
    (comp (ref "RF62")
      (value "1K")
      (footprint "RESC1005L-0.5")
      (description "Resistor")
      (fields (field (name "Comment") "Res1") (field (name "PUBLISHER") "Altium Limited"))
      (libsource (lib "Peace的集成库") (part "Res1"))
    )
    (comp (ref "RF63")
      (value "1K")
      (footprint "RESC1005L-0.5")
      (description "Resistor")
      (fields (field (name "Comment") "Res1") (field (name "PUBLISHER") "Altium Limited"))
      (libsource (lib "Peace的集成库") (part "Res1"))
    )
    (comp (ref "RF64")
      (value "1K")
      (footprint "RESC1005L-0.5")
      (description "Resistor")
      (fields (field (name "Comment") "Res1") (field (name "PUBLISHER") "Altium Limited"))
      (libsource (lib "Peace的集成库") (part "Res1"))
    )
    (comp (ref "RF65")
      (value "1K")
      (footprint "RESC1005L-0.5")
      (description "Resistor")
      (fields (field (name "Comment") "Res1") (field (name "PUBLISHER") "Altium Limited"))
      (libsource (lib "Peace的集成库") (part "Res1"))
    )
    (comp (ref "RF66")
      (value "1K")
      (footprint "RESC1005L-0.5")
      (description "Resistor")
      (fields (field (name "Comment") "Res1") (field (name "PUBLISHER") "Altium Limited"))
      (libsource (lib "Peace的集成库") (part "Res1"))
    )
    (comp (ref "RF67")
      (value "1K")
      (footprint "RESC1005L-0.5")
      (description "Resistor")
      (fields (field (name "Comment") "Res1") (field (name "PUBLISHER") "Altium Limited"))
      (libsource (lib "Peace的集成库") (part "Res1"))
    )
    (comp (ref "RF68")
      (value "1K")
      (footprint "RESC1005L-0.5")
      (description "Resistor")
      (fields (field (name "Comment") "Res1") (field (name "PUBLISHER") "Altium Limited"))
      (libsource (lib "Peace的集成库") (part "Res1"))
    )
    (comp (ref "RF69")
      (value "1K")
      (footprint "RESC1005L-0.5")
      (description "Resistor")
      (fields (field (name "Comment") "Res1") (field (name "PUBLISHER") "Altium Limited"))
      (libsource (lib "Peace的集成库") (part "Res1"))
    )
    (comp (ref "RF70")
      (value "1K")
      (footprint "RESC1005L-0.5")
      (description "Resistor")
      (fields (field (name "Comment") "Res1") (field (name "PUBLISHER") "Altium Limited"))
      (libsource (lib "Peace的集成库") (part "Res1"))
    )
    (comp (ref "RF71")
      (value "1K")
      (footprint "RESC1005L-0.5")
      (description "Resistor")
      (fields (field (name "Comment") "Res1") (field (name "PUBLISHER") "Altium Limited"))
      (libsource (lib "Peace的集成库") (part "Res1"))
    )
    (comp (ref "RF72")
      (value "1K")
      (footprint "RESC1005L-0.5")
      (description "Resistor")
      (fields (field (name "Comment") "Res1") (field (name "PUBLISHER") "Altium Limited"))
      (libsource (lib "Peace的集成库") (part "Res1"))
    )
    (comp (ref "RF73")
      (value "1K")
      (footprint "RESC1005L-0.5")
      (description "Resistor")
      (fields (field (name "Comment") "Res1") (field (name "PUBLISHER") "Altium Limited"))
      (libsource (lib "Peace的集成库") (part "Res1"))
    )
    (comp (ref "RF74")
      (value "1K")
      (footprint "RESC1005L-0.5")
      (description "Resistor")
      (fields (field (name "Comment") "Res1") (field (name "PUBLISHER") "Altium Limited"))
      (libsource (lib "Peace的集成库") (part "Res1"))
    )
    (comp (ref "RF75")
      (value "1K")
      (footprint "RESC1005L-0.5")
      (description "Resistor")
      (fields (field (name "Comment") "Res1") (field (name "PUBLISHER") "Altium Limited"))
      (libsource (lib "Peace的集成库") (part "Res1"))
    )
    (comp (ref "RF76")
      (value "1K")
      (footprint "RESC1005L-0.5")
      (description "Resistor")
      (fields (field (name "Comment") "Res1") (field (name "PUBLISHER") "Altium Limited"))
      (libsource (lib "Peace的集成库") (part "Res1"))
    )
    (comp (ref "RF77")
      (value "1K")
      (footprint "RESC1005L-0.5")
      (description "Resistor")
      (fields (field (name "Comment") "Res1") (field (name "PUBLISHER") "Altium Limited"))
      (libsource (lib "Peace的集成库") (part "Res1"))
    )
    (comp (ref "RF78")
      (value "1K")
      (footprint "RESC1005L-0.5")
      (description "Resistor")
      (fields (field (name "Comment") "Res1") (field (name "PUBLISHER") "Altium Limited"))
      (libsource (lib "Peace的集成库") (part "Res1"))
    )
    (comp (ref "RF79")
      (value "1K")
      (footprint "RESC1005L-0.5")
      (description "Resistor")
      (fields (field (name "Comment") "Res1") (field (name "PUBLISHER") "Altium Limited"))
      (libsource (lib "Peace的集成库") (part "Res1"))
    )
    (comp (ref "RF80")
      (value "1K")
      (footprint "RESC1005L-0.5")
      (description "Resistor")
      (fields (field (name "Comment") "Res1") (field (name "PUBLISHER") "Altium Limited"))
      (libsource (lib "Peace的集成库") (part "Res1"))
    )
    (comp (ref "RF81")
      (value "1K")
      (footprint "RESC1005L-0.5")
      (description "Resistor")
      (fields (field (name "Comment") "Res1") (field (name "PUBLISHER") "Altium Limited"))
      (libsource (lib "Peace的集成库") (part "Res1"))
    )
    (comp (ref "RF82")
      (value "1K")
      (footprint "RESC1005L-0.5")
      (description "Resistor")
      (fields (field (name "Comment") "Res1") (field (name "PUBLISHER") "Altium Limited"))
      (libsource (lib "Peace的集成库") (part "Res1"))
    )
    (comp (ref "RF83")
      (value "1K")
      (footprint "RESC1005L-0.5")
      (description "Resistor")
      (fields (field (name "Comment") "Res1") (field (name "PUBLISHER") "Altium Limited"))
      (libsource (lib "Peace的集成库") (part "Res1"))
    )
    (comp (ref "RF84")
      (value "1K")
      (footprint "RESC1005L-0.5")
      (description "Resistor")
      (fields (field (name "Comment") "Res1") (field (name "PUBLISHER") "Altium Limited"))
      (libsource (lib "Peace的集成库") (part "Res1"))
    )
    (comp (ref "RF85")
      (value "1K")
      (footprint "RESC1005L-0.5")
      (description "Resistor")
      (fields (field (name "Comment") "Res1") (field (name "PUBLISHER") "Altium Limited"))
      (libsource (lib "Peace的集成库") (part "Res1"))
    )
    (comp (ref "RF86")
      (value "1K")
      (footprint "RESC1005L-0.5")
      (description "Resistor")
      (fields (field (name "Comment") "Res1") (field (name "PUBLISHER") "Altium Limited"))
      (libsource (lib "Peace的集成库") (part "Res1"))
    )
    (comp (ref "RF87")
      (value "1K")
      (footprint "RESC1005L-0.5")
      (description "Resistor")
      (fields (field (name "Comment") "Res1") (field (name "PUBLISHER") "Altium Limited"))
      (libsource (lib "Peace的集成库") (part "Res1"))
    )
    (comp (ref "RF88")
      (value "1K")
      (footprint "RESC1005L-0.5")
      (description "Resistor")
      (fields (field (name "Comment") "Res1") (field (name "PUBLISHER") "Altium Limited"))
      (libsource (lib "Peace的集成库") (part "Res1"))
    )
    (comp (ref "RF89")
      (value "1K")
      (footprint "RESC1005L-0.5")
      (description "Resistor")
      (fields (field (name "Comment") "Res1") (field (name "PUBLISHER") "Altium Limited"))
      (libsource (lib "Peace的集成库") (part "Res1"))
    )
    (comp (ref "RF90")
      (value "1K")
      (footprint "RESC1005L-0.5")
      (description "Resistor")
      (fields (field (name "Comment") "Res1") (field (name "PUBLISHER") "Altium Limited"))
      (libsource (lib "Peace的集成库") (part "Res1"))
    )
    (comp (ref "RF91")
      (value "1K")
      (footprint "RESC1005L-0.5")
      (description "Resistor")
      (fields (field (name "Comment") "Res1") (field (name "PUBLISHER") "Altium Limited"))
      (libsource (lib "Peace的集成库") (part "Res1"))
    )
    (comp (ref "RF92")
      (value "1K")
      (footprint "RESC1005L-0.5")
      (description "Resistor")
      (fields (field (name "Comment") "Res1") (field (name "PUBLISHER") "Altium Limited"))
      (libsource (lib "Peace的集成库") (part "Res1"))
    )
    (comp (ref "RF93")
      (value "1K")
      (footprint "RESC1005L-0.5")
      (description "Resistor")
      (fields (field (name "Comment") "Res1") (field (name "PUBLISHER") "Altium Limited"))
      (libsource (lib "Peace的集成库") (part "Res1"))
    )
    (comp (ref "RF94")
      (value "1K")
      (footprint "RESC1005L-0.5")
      (description "Resistor")
      (fields (field (name "Comment") "Res1") (field (name "PUBLISHER") "Altium Limited"))
      (libsource (lib "Peace的集成库") (part "Res1"))
    )
    (comp (ref "RF95")
      (value "1K")
      (footprint "RESC1005L-0.5")
      (description "Resistor")
      (fields (field (name "Comment") "Res1") (field (name "PUBLISHER") "Altium Limited"))
      (libsource (lib "Peace的集成库") (part "Res1"))
    )
    (comp (ref "RF96")
      (value "1K")
      (footprint "RESC1005L-0.5")
      (description "Resistor")
      (fields (field (name "Comment") "Res1") (field (name "PUBLISHER") "Altium Limited"))
      (libsource (lib "Peace的集成库") (part "Res1"))
    )
    (comp (ref "RF97")
      (value "1K")
      (footprint "RESC1005L-0.5")
      (description "Resistor")
      (fields (field (name "Comment") "Res1") (field (name "PUBLISHER") "Altium Limited"))
      (libsource (lib "Peace的集成库") (part "Res1"))
    )
    (comp (ref "RF98")
      (value "1K")
      (footprint "RESC1005L-0.5")
      (description "Resistor")
      (fields (field (name "Comment") "Res1") (field (name "PUBLISHER") "Altium Limited"))
      (libsource (lib "Peace的集成库") (part "Res1"))
    )
    (comp (ref "RF99")
      (value "1K")
      (footprint "RESC1005L-0.5")
      (description "Resistor")
      (fields (field (name "Comment") "Res1") (field (name "PUBLISHER") "Altium Limited"))
      (libsource (lib "Peace的集成库") (part "Res1"))
    )
    (comp (ref "RF100")
      (value "1K")
      (footprint "RESC1005L-0.5")
      (description "Resistor")
      (fields (field (name "Comment") "Res1") (field (name "PUBLISHER") "Altium Limited"))
      (libsource (lib "Peace的集成库") (part "Res1"))
    )
    (comp (ref "RF101")
      (value "1K")
      (footprint "RESC1005L-0.5")
      (description "Resistor")
      (fields (field (name "Comment") "Res1") (field (name "PUBLISHER") "Altium Limited"))
      (libsource (lib "Peace的集成库") (part "Res1"))
    )
    (comp (ref "RF102")
      (value "1K")
      (footprint "RESC1005L-0.5")
      (description "Resistor")
      (fields (field (name "Comment") "Res1") (field (name "PUBLISHER") "Altium Limited"))
      (libsource (lib "Peace的集成库") (part "Res1"))
    )
    (comp (ref "RF103")
      (value "1K")
      (footprint "RESC1005L-0.5")
      (description "Resistor")
      (fields (field (name "Comment") "Res1") (field (name "PUBLISHER") "Altium Limited"))
      (libsource (lib "Peace的集成库") (part "Res1"))
    )
    (comp (ref "RF104")
      (value "1K")
      (footprint "RESC1005L-0.5")
      (description "Resistor")
      (fields (field (name "Comment") "Res1") (field (name "PUBLISHER") "Altium Limited"))
      (libsource (lib "Peace的集成库") (part "Res1"))
    )
    (comp (ref "RF105")
      (value "1K")
      (footprint "RESC1005L-0.5")
      (description "Resistor")
      (fields (field (name "Comment") "Res1") (field (name "PUBLISHER") "Altium Limited"))
      (libsource (lib "Peace的集成库") (part "Res1"))
    )
    (comp (ref "RF106")
      (value "1K")
      (footprint "RESC1005L-0.5")
      (description "Resistor")
      (fields (field (name "Comment") "Res1") (field (name "PUBLISHER") "Altium Limited"))
      (libsource (lib "Peace的集成库") (part "Res1"))
    )
    (comp (ref "RF107")
      (value "1K")
      (footprint "RESC1005L-0.5")
      (description "Resistor")
      (fields (field (name "Comment") "Res1") (field (name "PUBLISHER") "Altium Limited"))
      (libsource (lib "Peace的集成库") (part "Res1"))
    )
    (comp (ref "RF108")
      (value "1K")
      (footprint "RESC1005L-0.5")
      (description "Resistor")
      (fields (field (name "Comment") "Res1") (field (name "PUBLISHER") "Altium Limited"))
      (libsource (lib "Peace的集成库") (part "Res1"))
    )
    (comp (ref "RF109")
      (value "1K")
      (footprint "RESC1005L-0.5")
      (description "Resistor")
      (fields (field (name "Comment") "Res1") (field (name "PUBLISHER") "Altium Limited"))
      (libsource (lib "Peace的集成库") (part "Res1"))
    )
    (comp (ref "RF110")
      (value "1K")
      (footprint "RESC1005L-0.5")
      (description "Resistor")
      (fields (field (name "Comment") "Res1") (field (name "PUBLISHER") "Altium Limited"))
      (libsource (lib "Peace的集成库") (part "Res1"))
    )
    (comp (ref "RF111")
      (value "1K")
      (footprint "RESC1005L-0.5")
      (description "Resistor")
      (fields (field (name "Comment") "Res1") (field (name "PUBLISHER") "Altium Limited"))
      (libsource (lib "Peace的集成库") (part "Res1"))
    )
    (comp (ref "RF112")
      (value "1K")
      (footprint "RESC1005L-0.5")
      (description "Resistor")
      (fields (field (name "Comment") "Res1") (field (name "PUBLISHER") "Altium Limited"))
      (libsource (lib "Peace的集成库") (part "Res1"))
    )
    (comp (ref "RF113")
      (value "1K")
      (footprint "RESC1005L-0.5")
      (description "Resistor")
      (fields (field (name "Comment") "Res1") (field (name "PUBLISHER") "Altium Limited"))
      (libsource (lib "Peace的集成库") (part "Res1"))
    )
    (comp (ref "RF114")
      (value "1K")
      (footprint "RESC1005L-0.5")
      (description "Resistor")
      (fields (field (name "Comment") "Res1") (field (name "PUBLISHER") "Altium Limited"))
      (libsource (lib "Peace的集成库") (part "Res1"))
    )
    (comp (ref "RF115")
      (value "1K")
      (footprint "RESC1005L-0.5")
      (description "Resistor")
      (fields (field (name "Comment") "Res1") (field (name "PUBLISHER") "Altium Limited"))
      (libsource (lib "Peace的集成库") (part "Res1"))
    )
    (comp (ref "RF116")
      (value "1K")
      (footprint "RESC1005L-0.5")
      (description "Resistor")
      (fields (field (name "Comment") "Res1") (field (name "PUBLISHER") "Altium Limited"))
      (libsource (lib "Peace的集成库") (part "Res1"))
    )
    (comp (ref "RF117")
      (value "1K")
      (footprint "RESC1005L-0.5")
      (description "Resistor")
      (fields (field (name "Comment") "Res1") (field (name "PUBLISHER") "Altium Limited"))
      (libsource (lib "Peace的集成库") (part "Res1"))
    )
    (comp (ref "RF118")
      (value "1K")
      (footprint "RESC1005L-0.5")
      (description "Resistor")
      (fields (field (name "Comment") "Res1") (field (name "PUBLISHER") "Altium Limited"))
      (libsource (lib "Peace的集成库") (part "Res1"))
    )
    (comp (ref "RF119")
      (value "1K")
      (footprint "RESC1005L-0.5")
      (description "Resistor")
      (fields (field (name "Comment") "Res1") (field (name "PUBLISHER") "Altium Limited"))
      (libsource (lib "Peace的集成库") (part "Res1"))
    )
    (comp (ref "RF120")
      (value "1K")
      (footprint "RESC1005L-0.5")
      (description "Resistor")
      (fields (field (name "Comment") "Res1") (field (name "PUBLISHER") "Altium Limited"))
      (libsource (lib "Peace的集成库") (part "Res1"))
    )
    (comp (ref "RF121")
      (value "1K")
      (footprint "RESC1005L-0.5")
      (description "Resistor")
      (fields (field (name "Comment") "Res1") (field (name "PUBLISHER") "Altium Limited"))
      (libsource (lib "Peace的集成库") (part "Res1"))
    )
    (comp (ref "RF122")
      (value "1K")
      (footprint "RESC1005L-0.5")
      (description "Resistor")
      (fields (field (name "Comment") "Res1") (field (name "PUBLISHER") "Altium Limited"))
      (libsource (lib "Peace的集成库") (part "Res1"))
    )
    (comp (ref "RF123")
      (value "1K")
      (footprint "RESC1005L-0.5")
      (description "Resistor")
      (fields (field (name "Comment") "Res1") (field (name "PUBLISHER") "Altium Limited"))
      (libsource (lib "Peace的集成库") (part "Res1"))
    )
    (comp (ref "RF124")
      (value "1K")
      (footprint "RESC1005L-0.5")
      (description "Resistor")
      (fields (field (name "Comment") "Res1") (field (name "PUBLISHER") "Altium Limited"))
      (libsource (lib "Peace的集成库") (part "Res1"))
    )
    (comp (ref "RF125")
      (value "1K")
      (footprint "RESC1005L-0.5")
      (description "Resistor")
      (fields (field (name "Comment") "Res1") (field (name "PUBLISHER") "Altium Limited"))
      (libsource (lib "Peace的集成库") (part "Res1"))
    )
    (comp (ref "RF126")
      (value "1K")
      (footprint "RESC1005L-0.5")
      (description "Resistor")
      (fields (field (name "Comment") "Res1") (field (name "PUBLISHER") "Altium Limited"))
      (libsource (lib "Peace的集成库") (part "Res1"))
    )
    (comp (ref "RF127")
      (value "1K")
      (footprint "RESC1005L-0.5")
      (description "Resistor")
      (fields (field (name "Comment") "Res1") (field (name "PUBLISHER") "Altium Limited"))
      (libsource (lib "Peace的集成库") (part "Res1"))
    )
    (comp (ref "RF128")
      (value "1K")
      (footprint "RESC1005L-0.5")
      (description "Resistor")
      (fields (field (name "Comment") "Res1") (field (name "PUBLISHER") "Altium Limited"))
      (libsource (lib "Peace的集成库") (part "Res1"))
    )
    (comp (ref "UF1")
      (value "74HC595")
      (footprint "TSSOP-16N")
      (description "8-Bit Serial-Input/Serial or Prallel-Output Shift Register with Latched 3-State Outputs")
      (fields (field (name "PUBLISHER") "Altium Limited"))
      (libsource (lib "原理图库") (part "74HC595"))
    )
    (comp (ref "UF2")
      (value "74HC595")
      (footprint "TSSOP-16N")
      (description "8-Bit Serial-Input/Serial or Prallel-Output Shift Register with Latched 3-State Outputs")
      (fields (field (name "PUBLISHER") "Altium Limited"))
      (libsource (lib "原理图库") (part "74HC595"))
    )
    (comp (ref "UF3")
      (value "74HC595")
      (footprint "TSSOP-16N")
      (description "8-Bit Serial-Input/Serial or Prallel-Output Shift Register with Latched 3-State Outputs")
      (fields (field (name "PUBLISHER") "Altium Limited"))
      (libsource (lib "原理图库") (part "74HC595"))
    )
    (comp (ref "UF4")
      (value "74HC595")
      (footprint "TSSOP-16N")
      (description "8-Bit Serial-Input/Serial or Prallel-Output Shift Register with Latched 3-State Outputs")
      (fields (field (name "PUBLISHER") "Altium Limited"))
      (libsource (lib "原理图库") (part "74HC595"))
    )
    (comp (ref "UF5")
      (value "74HC595")
      (footprint "TSSOP-16N")
      (description "8-Bit Serial-Input/Serial or Prallel-Output Shift Register with Latched 3-State Outputs")
      (fields (field (name "PUBLISHER") "Altium Limited"))
      (libsource (lib "原理图库") (part "74HC595"))
    )
    (comp (ref "UF6")
      (value "74HC595")
      (footprint "TSSOP-16N")
      (description "8-Bit Serial-Input/Serial or Prallel-Output Shift Register with Latched 3-State Outputs")
      (fields (field (name "PUBLISHER") "Altium Limited"))
      (libsource (lib "原理图库") (part "74HC595"))
    )
    (comp (ref "UF7")
      (value "74HC595")
      (footprint "TSSOP-16N")
      (description "8-Bit Serial-Input/Serial or Prallel-Output Shift Register with Latched 3-State Outputs")
      (fields (field (name "PUBLISHER") "Altium Limited"))
      (libsource (lib "原理图库") (part "74HC595"))
    )
    (comp (ref "UF8")
      (value "74HC595")
      (footprint "TSSOP-16N")
      (description "8-Bit Serial-Input/Serial or Prallel-Output Shift Register with Latched 3-State Outputs")
      (fields (field (name "PUBLISHER") "Altium Limited"))
      (libsource (lib "原理图库") (part "74HC595"))
    )
    (comp (ref "UF9")
      (value "74HC595")
      (footprint "TSSOP-16N")
      (description "8-Bit Serial-Input/Serial or Prallel-Output Shift Register with Latched 3-State Outputs")
      (fields (field (name "PUBLISHER") "Altium Limited"))
      (libsource (lib "原理图库") (part "74HC595"))
    )
    (comp (ref "UF10")
      (value "74HC595")
      (footprint "TSSOP-16N")
      (description "8-Bit Serial-Input/Serial or Prallel-Output Shift Register with Latched 3-State Outputs")
      (fields (field (name "PUBLISHER") "Altium Limited"))
      (libsource (lib "原理图库") (part "74HC595"))
    )
    (comp (ref "UF11")
      (value "74HC595")
      (footprint "TSSOP-16N")
      (description "8-Bit Serial-Input/Serial or Prallel-Output Shift Register with Latched 3-State Outputs")
      (fields (field (name "PUBLISHER") "Altium Limited"))
      (libsource (lib "原理图库") (part "74HC595"))
    )
    (comp (ref "UF12")
      (value "74HC595")
      (footprint "TSSOP-16N")
      (description "8-Bit Serial-Input/Serial or Prallel-Output Shift Register with Latched 3-State Outputs")
      (fields (field (name "PUBLISHER") "Altium Limited"))
      (libsource (lib "原理图库") (part "74HC595"))
    )
    (comp (ref "UF13")
      (value "74HC595")
      (footprint "TSSOP-16N")
      (description "8-Bit Serial-Input/Serial or Prallel-Output Shift Register with Latched 3-State Outputs")
      (fields (field (name "PUBLISHER") "Altium Limited"))
      (libsource (lib "原理图库") (part "74HC595"))
    )
    (comp (ref "UF14")
      (value "74HC595")
      (footprint "TSSOP-16N")
      (description "8-Bit Serial-Input/Serial or Prallel-Output Shift Register with Latched 3-State Outputs")
      (fields (field (name "PUBLISHER") "Altium Limited"))
      (libsource (lib "原理图库") (part "74HC595"))
    )
    (comp (ref "UF15")
      (value "74HC595")
      (footprint "TSSOP-16N")
      (description "8-Bit Serial-Input/Serial or Prallel-Output Shift Register with Latched 3-State Outputs")
      (fields (field (name "PUBLISHER") "Altium Limited"))
      (libsource (lib "原理图库") (part "74HC595"))
    )
    (comp (ref "UF16")
      (value "74HC595")
      (footprint "TSSOP-16N")
      (description "8-Bit Serial-Input/Serial or Prallel-Output Shift Register with Latched 3-State Outputs")
      (fields (field (name "PUBLISHER") "Altium Limited"))
      (libsource (lib "原理图库") (part "74HC595"))
    )
  )
  (nets
    (net (code "1") (name "+5V") (class "Default")
      (node (ref "CF1") (pin "2") (pinfunction "2_2") (pintype "passive"))
      (node (ref "CF10") (pin "2") (pinfunction "2_2") (pintype "passive"))
      (node (ref "CF11") (pin "2") (pinfunction "2_2") (pintype "passive"))
      (node (ref "CF12") (pin "2") (pinfunction "2_2") (pintype "passive"))
      (node (ref "CF13") (pin "2") (pinfunction "2_2") (pintype "passive"))
      (node (ref "CF14") (pin "2") (pinfunction "2_2") (pintype "passive"))
      (node (ref "CF15") (pin "2") (pinfunction "2_2") (pintype "passive"))
      (node (ref "CF16") (pin "2") (pinfunction "2_2") (pintype "passive"))
      (node (ref "CF2") (pin "2") (pinfunction "2_2") (pintype "passive"))
      (node (ref "CF3") (pin "2") (pinfunction "2_2") (pintype "passive"))
      (node (ref "CF4") (pin "2") (pinfunction "2_2") (pintype "passive"))
      (node (ref "CF5") (pin "2") (pinfunction "2_2") (pintype "passive"))
      (node (ref "CF6") (pin "2") (pinfunction "2_2") (pintype "passive"))
      (node (ref "CF7") (pin "2") (pinfunction "2_2") (pintype "passive"))
      (node (ref "CF8") (pin "2") (pinfunction "2_2") (pintype "passive"))
      (node (ref "CF9") (pin "2") (pinfunction "2_2") (pintype "passive"))
      (node (ref "UF1") (pin "16") (pinfunction "VDD_16") (pintype "power_in"))
      (node (ref "UF10") (pin "16") (pinfunction "VDD_16") (pintype "power_in"))
      (node (ref "UF11") (pin "16") (pinfunction "VDD_16") (pintype "power_in"))
      (node (ref "UF12") (pin "16") (pinfunction "VDD_16") (pintype "power_in"))
      (node (ref "UF13") (pin "16") (pinfunction "VDD_16") (pintype "power_in"))
      (node (ref "UF14") (pin "16") (pinfunction "VDD_16") (pintype "power_in"))
      (node (ref "UF15") (pin "16") (pinfunction "VDD_16") (pintype "power_in"))
      (node (ref "UF16") (pin "16") (pinfunction "VDD_16") (pintype "power_in"))
      (node (ref "UF2") (pin "16") (pinfunction "VDD_16") (pintype "power_in"))
      (node (ref "UF3") (pin "16") (pinfunction "VDD_16") (pintype "power_in"))
      (node (ref "UF4") (pin "16") (pinfunction "VDD_16") (pintype "power_in"))
      (node (ref "UF5") (pin "16") (pinfunction "VDD_16") (pintype "power_in"))
      (node (ref "UF6") (pin "16") (pinfunction "VDD_16") (pintype "power_in"))
      (node (ref "UF7") (pin "16") (pinfunction "VDD_16") (pintype "power_in"))
      (node (ref "UF8") (pin "16") (pinfunction "VDD_16") (pintype "power_in"))
      (node (ref "UF9") (pin "16") (pinfunction "VDD_16") (pintype "power_in"))
    )
    (net (code "2") (name "/CS") (class "Default")
      (node (ref "UF1") (pin "12") (pinfunction "LCHCLK_12") (pintype "input"))
      (node (ref "UF10") (pin "12") (pinfunction "LCHCLK_12") (pintype "input"))
      (node (ref "UF11") (pin "12") (pinfunction "LCHCLK_12") (pintype "input"))
      (node (ref "UF12") (pin "12") (pinfunction "LCHCLK_12") (pintype "input"))
      (node (ref "UF13") (pin "12") (pinfunction "LCHCLK_12") (pintype "input"))
      (node (ref "UF14") (pin "12") (pinfunction "LCHCLK_12") (pintype "input"))
      (node (ref "UF15") (pin "12") (pinfunction "LCHCLK_12") (pintype "input"))
      (node (ref "UF16") (pin "12") (pinfunction "LCHCLK_12") (pintype "input"))
      (node (ref "UF2") (pin "12") (pinfunction "LCHCLK_12") (pintype "input"))
      (node (ref "UF3") (pin "12") (pinfunction "LCHCLK_12") (pintype "input"))
      (node (ref "UF4") (pin "12") (pinfunction "LCHCLK_12") (pintype "input"))
      (node (ref "UF5") (pin "12") (pinfunction "LCHCLK_12") (pintype "input"))
      (node (ref "UF6") (pin "12") (pinfunction "LCHCLK_12") (pintype "input"))
      (node (ref "UF7") (pin "12") (pinfunction "LCHCLK_12") (pintype "input"))
      (node (ref "UF8") (pin "12") (pinfunction "LCHCLK_12") (pintype "input"))
      (node (ref "UF9") (pin "12") (pinfunction "LCHCLK_12") (pintype "input"))
    )
    (net (code "3") (name "/PWM") (class "Default")
      (node (ref "UF1") (pin "13") (pinfunction "~{OE}_13") (pintype "input"))
      (node (ref "UF10") (pin "13") (pinfunction "~{OE}_13") (pintype "input"))
      (node (ref "UF11") (pin "13") (pinfunction "~{OE}_13") (pintype "input"))
      (node (ref "UF12") (pin "13") (pinfunction "~{OE}_13") (pintype "input"))
      (node (ref "UF13") (pin "13") (pinfunction "~{OE}_13") (pintype "input"))
      (node (ref "UF14") (pin "13") (pinfunction "~{OE}_13") (pintype "input"))
      (node (ref "UF15") (pin "13") (pinfunction "~{OE}_13") (pintype "input"))
      (node (ref "UF16") (pin "13") (pinfunction "~{OE}_13") (pintype "input"))
      (node (ref "UF2") (pin "13") (pinfunction "~{OE}_13") (pintype "input"))
      (node (ref "UF3") (pin "13") (pinfunction "~{OE}_13") (pintype "input"))
      (node (ref "UF4") (pin "13") (pinfunction "~{OE}_13") (pintype "input"))
      (node (ref "UF5") (pin "13") (pinfunction "~{OE}_13") (pintype "input"))
      (node (ref "UF6") (pin "13") (pinfunction "~{OE}_13") (pintype "input"))
      (node (ref "UF7") (pin "13") (pinfunction "~{OE}_13") (pintype "input"))
      (node (ref "UF8") (pin "13") (pinfunction "~{OE}_13") (pintype "input"))
      (node (ref "UF9") (pin "13") (pinfunction "~{OE}_13") (pintype "input"))
    )
    (net (code "4") (name "/RST") (class "Default")
      (node (ref "UF1") (pin "10") (pinfunction "~{RST}_10") (pintype "input"))
      (node (ref "UF10") (pin "10") (pinfunction "~{RST}_10") (pintype "input"))
      (node (ref "UF11") (pin "10") (pinfunction "~{RST}_10") (pintype "input"))
      (node (ref "UF12") (pin "10") (pinfunction "~{RST}_10") (pintype "input"))
      (node (ref "UF13") (pin "10") (pinfunction "~{RST}_10") (pintype "input"))
      (node (ref "UF14") (pin "10") (pinfunction "~{RST}_10") (pintype "input"))
      (node (ref "UF15") (pin "10") (pinfunction "~{RST}_10") (pintype "input"))
      (node (ref "UF16") (pin "10") (pinfunction "~{RST}_10") (pintype "input"))
      (node (ref "UF2") (pin "10") (pinfunction "~{RST}_10") (pintype "input"))
      (node (ref "UF3") (pin "10") (pinfunction "~{RST}_10") (pintype "input"))
      (node (ref "UF4") (pin "10") (pinfunction "~{RST}_10") (pintype "input"))
      (node (ref "UF5") (pin "10") (pinfunction "~{RST}_10") (pintype "input"))
      (node (ref "UF6") (pin "10") (pinfunction "~{RST}_10") (pintype "input"))
      (node (ref "UF7") (pin "10") (pinfunction "~{RST}_10") (pintype "input"))
      (node (ref "UF8") (pin "10") (pinfunction "~{RST}_10") (pintype "input"))
      (node (ref "UF9") (pin "10") (pinfunction "~{RST}_10") (pintype "input"))
    )
    (net (code "5") (name "/SCLK") (class "Default")
      (node (ref "UF1") (pin "11") (pinfunction "SFTCLK_11") (pintype "input"))
      (node (ref "UF10") (pin "11") (pinfunction "SFTCLK_11") (pintype "input"))
      (node (ref "UF11") (pin "11") (pinfunction "SFTCLK_11") (pintype "input"))
      (node (ref "UF12") (pin "11") (pinfunction "SFTCLK_11") (pintype "input"))
      (node (ref "UF13") (pin "11") (pinfunction "SFTCLK_11") (pintype "input"))
      (node (ref "UF14") (pin "11") (pinfunction "SFTCLK_11") (pintype "input"))
      (node (ref "UF15") (pin "11") (pinfunction "SFTCLK_11") (pintype "input"))
      (node (ref "UF16") (pin "11") (pinfunction "SFTCLK_11") (pintype "input"))
      (node (ref "UF2") (pin "11") (pinfunction "SFTCLK_11") (pintype "input"))
      (node (ref "UF3") (pin "11") (pinfunction "SFTCLK_11") (pintype "input"))
      (node (ref "UF4") (pin "11") (pinfunction "SFTCLK_11") (pintype "input"))
      (node (ref "UF5") (pin "11") (pinfunction "SFTCLK_11") (pintype "input"))
      (node (ref "UF6") (pin "11") (pinfunction "SFTCLK_11") (pintype "input"))
      (node (ref "UF7") (pin "11") (pinfunction "SFTCLK_11") (pintype "input"))
      (node (ref "UF8") (pin "11") (pinfunction "SFTCLK_11") (pintype "input"))
      (node (ref "UF9") (pin "11") (pinfunction "SFTCLK_11") (pintype "input"))
    )
    (net (code "6") (name "/SDI") (class "Default")
      (node (ref "UF16") (pin "14") (pinfunction "SDI_14") (pintype "input"))
    )
    (net (code "8") (name "/SDO9") (class "Default")
      (node (ref "UF1") (pin "14") (pinfunction "SDI_14") (pintype "input"))
      (node (ref "UF2") (pin "9") (pinfunction "SDO_9") (pintype "output"))
    )
    (net (code "9") (name "/SDO17") (class "Default")
      (node (ref "UF2") (pin "14") (pinfunction "SDI_14") (pintype "input"))
      (node (ref "UF3") (pin "9") (pinfunction "SDO_9") (pintype "output"))
    )
    (net (code "10") (name "/SDO25") (class "Default")
      (node (ref "UF3") (pin "14") (pinfunction "SDI_14") (pintype "input"))
      (node (ref "UF4") (pin "9") (pinfunction "SDO_9") (pintype "output"))
    )
    (net (code "11") (name "/SDO33") (class "Default")
      (node (ref "UF4") (pin "14") (pinfunction "SDI_14") (pintype "input"))
      (node (ref "UF5") (pin "9") (pinfunction "SDO_9") (pintype "output"))
    )
    (net (code "12") (name "/SDO41") (class "Default")
      (node (ref "UF5") (pin "14") (pinfunction "SDI_14") (pintype "input"))
      (node (ref "UF6") (pin "9") (pinfunction "SDO_9") (pintype "output"))
    )
    (net (code "13") (name "/SDO49") (class "Default")
      (node (ref "UF6") (pin "14") (pinfunction "SDI_14") (pintype "input"))
      (node (ref "UF7") (pin "9") (pinfunction "SDO_9") (pintype "output"))
    )
    (net (code "14") (name "/SDO57") (class "Default")
      (node (ref "UF7") (pin "14") (pinfunction "SDI_14") (pintype "input"))
      (node (ref "UF8") (pin "9") (pinfunction "SDO_9") (pintype "output"))
    )
    (net (code "15") (name "/SDO65") (class "Default")
      (node (ref "UF8") (pin "14") (pinfunction "SDI_14") (pintype "input"))
      (node (ref "UF9") (pin "9") (pinfunction "SDO_9") (pintype "output"))
    )
    (net (code "16") (name "/SDO73") (class "Default")
      (node (ref "UF10") (pin "9") (pinfunction "SDO_9") (pintype "output"))
      (node (ref "UF9") (pin "14") (pinfunction "SDI_14") (pintype "input"))
    )
    (net (code "17") (name "/SDO81") (class "Default")
      (node (ref "UF10") (pin "14") (pinfunction "SDI_14") (pintype "input"))
      (node (ref "UF11") (pin "9") (pinfunction "SDO_9") (pintype "output"))
    )
    (net (code "18") (name "/SDO89") (class "Default")
      (node (ref "UF11") (pin "14") (pinfunction "SDI_14") (pintype "input"))
      (node (ref "UF12") (pin "9") (pinfunction "SDO_9") (pintype "output"))
    )
    (net (code "19") (name "/SDO97") (class "Default")
      (node (ref "UF12") (pin "14") (pinfunction "SDI_14") (pintype "input"))
      (node (ref "UF13") (pin "9") (pinfunction "SDO_9") (pintype "output"))
    )
    (net (code "20") (name "/SDO105") (class "Default")
      (node (ref "UF13") (pin "14") (pinfunction "SDI_14") (pintype "input"))
      (node (ref "UF14") (pin "9") (pinfunction "SDO_9") (pintype "output"))
    )
    (net (code "21") (name "/SDO113") (class "Default")
      (node (ref "UF14") (pin "14") (pinfunction "SDI_14") (pintype "input"))
      (node (ref "UF15") (pin "9") (pinfunction "SDO_9") (pintype "output"))
    )
    (net (code "22") (name "/SDO121") (class "Default")
      (node (ref "UF15") (pin "14") (pinfunction "SDI_14") (pintype "input"))
      (node (ref "UF16") (pin "9") (pinfunction "SDO_9") (pintype "output"))
    )
    (net (code "23") (name "GND") (class "Default")
      (node (ref "CF1") (pin "1") (pinfunction "1_1") (pintype "passive"))
      (node (ref "CF10") (pin "1") (pinfunction "1_1") (pintype "passive"))
      (node (ref "CF11") (pin "1") (pinfunction "1_1") (pintype "passive"))
      (node (ref "CF12") (pin "1") (pinfunction "1_1") (pintype "passive"))
      (node (ref "CF13") (pin "1") (pinfunction "1_1") (pintype "passive"))
      (node (ref "CF14") (pin "1") (pinfunction "1_1") (pintype "passive"))
      (node (ref "CF15") (pin "1") (pinfunction "1_1") (pintype "passive"))
      (node (ref "CF16") (pin "1") (pinfunction "1_1") (pintype "passive"))
      (node (ref "CF2") (pin "1") (pinfunction "1_1") (pintype "passive"))
      (node (ref "CF3") (pin "1") (pinfunction "1_1") (pintype "passive"))
      (node (ref "CF4") (pin "1") (pinfunction "1_1") (pintype "passive"))
      (node (ref "CF5") (pin "1") (pinfunction "1_1") (pintype "passive"))
      (node (ref "CF6") (pin "1") (pinfunction "1_1") (pintype "passive"))
      (node (ref "CF7") (pin "1") (pinfunction "1_1") (pintype "passive"))
      (node (ref "CF8") (pin "1") (pinfunction "1_1") (pintype "passive"))
      (node (ref "CF9") (pin "1") (pinfunction "1_1") (pintype "passive"))
      (node (ref "DF1") (pin "2") (pinfunction "K_2") (pintype "passive"))
      (node (ref "DF10") (pin "2") (pinfunction "K_2") (pintype "passive"))
      (node (ref "DF100") (pin "2") (pinfunction "K_2") (pintype "passive"))
      (node (ref "DF101") (pin "2") (pinfunction "K_2") (pintype "passive"))
      (node (ref "DF102") (pin "2") (pinfunction "K_2") (pintype "passive"))
      (node (ref "DF103") (pin "2") (pinfunction "K_2") (pintype "passive"))
      (node (ref "DF104") (pin "2") (pinfunction "K_2") (pintype "passive"))
      (node (ref "DF105") (pin "2") (pinfunction "K_2") (pintype "passive"))
      (node (ref "DF106") (pin "2") (pinfunction "K_2") (pintype "passive"))
      (node (ref "DF107") (pin "2") (pinfunction "K_2") (pintype "passive"))
      (node (ref "DF108") (pin "2") (pinfunction "K_2") (pintype "passive"))
      (node (ref "DF109") (pin "2") (pinfunction "K_2") (pintype "passive"))
      (node (ref "DF11") (pin "2") (pinfunction "K_2") (pintype "passive"))
      (node (ref "DF110") (pin "2") (pinfunction "K_2") (pintype "passive"))
      (node (ref "DF111") (pin "2") (pinfunction "K_2") (pintype "passive"))
      (node (ref "DF112") (pin "2") (pinfunction "K_2") (pintype "passive"))
      (node (ref "DF113") (pin "2") (pinfunction "K_2") (pintype "passive"))
      (node (ref "DF114") (pin "2") (pinfunction "K_2") (pintype "passive"))
      (node (ref "DF115") (pin "2") (pinfunction "K_2") (pintype "passive"))
      (node (ref "DF116") (pin "2") (pinfunction "K_2") (pintype "passive"))
      (node (ref "DF117") (pin "2") (pinfunction "K_2") (pintype "passive"))
      (node (ref "DF118") (pin "2") (pinfunction "K_2") (pintype "passive"))
      (node (ref "DF119") (pin "2") (pinfunction "K_2") (pintype "passive"))
      (node (ref "DF12") (pin "2") (pinfunction "K_2") (pintype "passive"))
      (node (ref "DF120") (pin "2") (pinfunction "K_2") (pintype "passive"))
      (node (ref "DF121") (pin "2") (pinfunction "K_2") (pintype "passive"))
      (node (ref "DF122") (pin "2") (pinfunction "K_2") (pintype "passive"))
      (node (ref "DF123") (pin "2") (pinfunction "K_2") (pintype "passive"))
      (node (ref "DF124") (pin "2") (pinfunction "K_2") (pintype "passive"))
      (node (ref "DF125") (pin "2") (pinfunction "K_2") (pintype "passive"))
      (node (ref "DF126") (pin "2") (pinfunction "K_2") (pintype "passive"))
      (node (ref "DF127") (pin "2") (pinfunction "K_2") (pintype "passive"))
      (node (ref "DF128") (pin "2") (pinfunction "K_2") (pintype "passive"))
      (node (ref "DF13") (pin "2") (pinfunction "K_2") (pintype "passive"))
      (node (ref "DF14") (pin "2") (pinfunction "K_2") (pintype "passive"))
      (node (ref "DF15") (pin "2") (pinfunction "K_2") (pintype "passive"))
      (node (ref "DF16") (pin "2") (pinfunction "K_2") (pintype "passive"))
      (node (ref "DF17") (pin "2") (pinfunction "K_2") (pintype "passive"))
      (node (ref "DF18") (pin "2") (pinfunction "K_2") (pintype "passive"))
      (node (ref "DF19") (pin "2") (pinfunction "K_2") (pintype "passive"))
      (node (ref "DF2") (pin "2") (pinfunction "K_2") (pintype "passive"))
      (node (ref "DF20") (pin "2") (pinfunction "K_2") (pintype "passive"))
      (node (ref "DF21") (pin "2") (pinfunction "K_2") (pintype "passive"))
      (node (ref "DF22") (pin "2") (pinfunction "K_2") (pintype "passive"))
      (node (ref "DF23") (pin "2") (pinfunction "K_2") (pintype "passive"))
      (node (ref "DF24") (pin "2") (pinfunction "K_2") (pintype "passive"))
      (node (ref "DF25") (pin "2") (pinfunction "K_2") (pintype "passive"))
      (node (ref "DF26") (pin "2") (pinfunction "K_2") (pintype "passive"))
      (node (ref "DF27") (pin "2") (pinfunction "K_2") (pintype "passive"))
      (node (ref "DF28") (pin "2") (pinfunction "K_2") (pintype "passive"))
      (node (ref "DF29") (pin "2") (pinfunction "K_2") (pintype "passive"))
      (node (ref "DF3") (pin "2") (pinfunction "K_2") (pintype "passive"))
      (node (ref "DF30") (pin "2") (pinfunction "K_2") (pintype "passive"))
      (node (ref "DF31") (pin "2") (pinfunction "K_2") (pintype "passive"))
      (node (ref "DF32") (pin "2") (pinfunction "K_2") (pintype "passive"))
      (node (ref "DF33") (pin "2") (pinfunction "K_2") (pintype "passive"))
      (node (ref "DF34") (pin "2") (pinfunction "K_2") (pintype "passive"))
      (node (ref "DF35") (pin "2") (pinfunction "K_2") (pintype "passive"))
      (node (ref "DF36") (pin "2") (pinfunction "K_2") (pintype "passive"))
      (node (ref "DF37") (pin "2") (pinfunction "K_2") (pintype "passive"))
      (node (ref "DF38") (pin "2") (pinfunction "K_2") (pintype "passive"))
      (node (ref "DF39") (pin "2") (pinfunction "K_2") (pintype "passive"))
      (node (ref "DF4") (pin "2") (pinfunction "K_2") (pintype "passive"))
      (node (ref "DF40") (pin "2") (pinfunction "K_2") (pintype "passive"))
      (node (ref "DF41") (pin "2") (pinfunction "K_2") (pintype "passive"))
      (node (ref "DF42") (pin "2") (pinfunction "K_2") (pintype "passive"))
      (node (ref "DF43") (pin "2") (pinfunction "K_2") (pintype "passive"))
      (node (ref "DF44") (pin "2") (pinfunction "K_2") (pintype "passive"))
      (node (ref "DF45") (pin "2") (pinfunction "K_2") (pintype "passive"))
      (node (ref "DF46") (pin "2") (pinfunction "K_2") (pintype "passive"))
      (node (ref "DF47") (pin "2") (pinfunction "K_2") (pintype "passive"))
      (node (ref "DF48") (pin "2") (pinfunction "K_2") (pintype "passive"))
      (node (ref "DF49") (pin "2") (pinfunction "K_2") (pintype "passive"))
      (node (ref "DF5") (pin "2") (pinfunction "K_2") (pintype "passive"))
      (node (ref "DF50") (pin "2") (pinfunction "K_2") (pintype "passive"))
      (node (ref "DF51") (pin "2") (pinfunction "K_2") (pintype "passive"))
      (node (ref "DF52") (pin "2") (pinfunction "K_2") (pintype "passive"))
      (node (ref "DF53") (pin "2") (pinfunction "K_2") (pintype "passive"))
      (node (ref "DF54") (pin "2") (pinfunction "K_2") (pintype "passive"))
      (node (ref "DF55") (pin "2") (pinfunction "K_2") (pintype "passive"))
      (node (ref "DF56") (pin "2") (pinfunction "K_2") (pintype "passive"))
      (node (ref "DF57") (pin "2") (pinfunction "K_2") (pintype "passive"))
      (node (ref "DF58") (pin "2") (pinfunction "K_2") (pintype "passive"))
      (node (ref "DF59") (pin "2") (pinfunction "K_2") (pintype "passive"))
      (node (ref "DF6") (pin "2") (pinfunction "K_2") (pintype "passive"))
      (node (ref "DF60") (pin "2") (pinfunction "K_2") (pintype "passive"))
      (node (ref "DF61") (pin "2") (pinfunction "K_2") (pintype "passive"))
      (node (ref "DF62") (pin "2") (pinfunction "K_2") (pintype "passive"))
      (node (ref "DF63") (pin "2") (pinfunction "K_2") (pintype "passive"))
      (node (ref "DF64") (pin "2") (pinfunction "K_2") (pintype "passive"))
      (node (ref "DF65") (pin "2") (pinfunction "K_2") (pintype "passive"))
      (node (ref "DF66") (pin "2") (pinfunction "K_2") (pintype "passive"))
      (node (ref "DF67") (pin "2") (pinfunction "K_2") (pintype "passive"))
      (node (ref "DF68") (pin "2") (pinfunction "K_2") (pintype "passive"))
      (node (ref "DF69") (pin "2") (pinfunction "K_2") (pintype "passive"))
      (node (ref "DF7") (pin "2") (pinfunction "K_2") (pintype "passive"))
      (node (ref "DF70") (pin "2") (pinfunction "K_2") (pintype "passive"))
      (node (ref "DF71") (pin "2") (pinfunction "K_2") (pintype "passive"))
      (node (ref "DF72") (pin "2") (pinfunction "K_2") (pintype "passive"))
      (node (ref "DF73") (pin "2") (pinfunction "K_2") (pintype "passive"))
      (node (ref "DF74") (pin "2") (pinfunction "K_2") (pintype "passive"))
      (node (ref "DF75") (pin "2") (pinfunction "K_2") (pintype "passive"))
      (node (ref "DF76") (pin "2") (pinfunction "K_2") (pintype "passive"))
      (node (ref "DF77") (pin "2") (pinfunction "K_2") (pintype "passive"))
      (node (ref "DF78") (pin "2") (pinfunction "K_2") (pintype "passive"))
      (node (ref "DF79") (pin "2") (pinfunction "K_2") (pintype "passive"))
      (node (ref "DF8") (pin "2") (pinfunction "K_2") (pintype "passive"))
      (node (ref "DF80") (pin "2") (pinfunction "K_2") (pintype "passive"))
      (node (ref "DF81") (pin "2") (pinfunction "K_2") (pintype "passive"))
      (node (ref "DF82") (pin "2") (pinfunction "K_2") (pintype "passive"))
      (node (ref "DF83") (pin "2") (pinfunction "K_2") (pintype "passive"))
      (node (ref "DF84") (pin "2") (pinfunction "K_2") (pintype "passive"))
      (node (ref "DF85") (pin "2") (pinfunction "K_2") (pintype "passive"))
      (node (ref "DF86") (pin "2") (pinfunction "K_2") (pintype "passive"))
      (node (ref "DF87") (pin "2") (pinfunction "K_2") (pintype "passive"))
      (node (ref "DF88") (pin "2") (pinfunction "K_2") (pintype "passive"))
      (node (ref "DF89") (pin "2") (pinfunction "K_2") (pintype "passive"))
      (node (ref "DF9") (pin "2") (pinfunction "K_2") (pintype "passive"))
      (node (ref "DF90") (pin "2") (pinfunction "K_2") (pintype "passive"))
      (node (ref "DF91") (pin "2") (pinfunction "K_2") (pintype "passive"))
      (node (ref "DF92") (pin "2") (pinfunction "K_2") (pintype "passive"))
      (node (ref "DF93") (pin "2") (pinfunction "K_2") (pintype "passive"))
      (node (ref "DF94") (pin "2") (pinfunction "K_2") (pintype "passive"))
      (node (ref "DF95") (pin "2") (pinfunction "K_2") (pintype "passive"))
      (node (ref "DF96") (pin "2") (pinfunction "K_2") (pintype "passive"))
      (node (ref "DF97") (pin "2") (pinfunction "K_2") (pintype "passive"))
      (node (ref "DF98") (pin "2") (pinfunction "K_2") (pintype "passive"))
      (node (ref "DF99") (pin "2") (pinfunction "K_2") (pintype "passive"))
      (node (ref "UF1") (pin "8") (pinfunction "GND_8") (pintype "power_in"))
      (node (ref "UF10") (pin "8") (pinfunction "GND_8") (pintype "power_in"))
      (node (ref "UF11") (pin "8") (pinfunction "GND_8") (pintype "power_in"))
      (node (ref "UF12") (pin "8") (pinfunction "GND_8") (pintype "power_in"))
      (node (ref "UF13") (pin "8") (pinfunction "GND_8") (pintype "power_in"))
      (node (ref "UF14") (pin "8") (pinfunction "GND_8") (pintype "power_in"))
      (node (ref "UF15") (pin "8") (pinfunction "GND_8") (pintype "power_in"))
      (node (ref "UF16") (pin "8") (pinfunction "GND_8") (pintype "power_in"))
      (node (ref "UF2") (pin "8") (pinfunction "GND_8") (pintype "power_in"))
      (node (ref "UF3") (pin "8") (pinfunction "GND_8") (pintype "power_in"))
      (node (ref "UF4") (pin "8") (pinfunction "GND_8") (pintype "power_in"))
      (node (ref "UF5") (pin "8") (pinfunction "GND_8") (pintype "power_in"))
      (node (ref "UF6") (pin "8") (pinfunction "GND_8") (pintype "power_in"))
      (node (ref "UF7") (pin "8") (pinfunction "GND_8") (pintype "power_in"))
      (node (ref "UF8") (pin "8") (pinfunction "GND_8") (pintype "power_in"))
      (node (ref "UF9") (pin "8") (pinfunction "GND_8") (pintype "power_in"))
    )
    (net (code "24") (name "Net-(DF1-A)") (class "Default")
      (node (ref "DF1") (pin "1") (pinfunction "A_1") (pintype "passive"))
      (node (ref "RF1") (pin "2") (pinfunction "2_2") (pintype "passive"))
    )
    (net (code "25") (name "Net-(DF2-A)") (class "Default")
      (node (ref "DF2") (pin "1") (pinfunction "A_1") (pintype "passive"))
      (node (ref "RF2") (pin "2") (pinfunction "2_2") (pintype "passive"))
    )
    (net (code "26") (name "Net-(DF3-A)") (class "Default")
      (node (ref "DF3") (pin "1") (pinfunction "A_1") (pintype "passive"))
      (node (ref "RF3") (pin "2") (pinfunction "2_2") (pintype "passive"))
    )
    (net (code "27") (name "Net-(DF4-A)") (class "Default")
      (node (ref "DF4") (pin "1") (pinfunction "A_1") (pintype "passive"))
      (node (ref "RF4") (pin "2") (pinfunction "2_2") (pintype "passive"))
    )
    (net (code "28") (name "Net-(DF5-A)") (class "Default")
      (node (ref "DF5") (pin "1") (pinfunction "A_1") (pintype "passive"))
      (node (ref "RF5") (pin "2") (pinfunction "2_2") (pintype "passive"))
    )
    (net (code "29") (name "Net-(DF6-A)") (class "Default")
      (node (ref "DF6") (pin "1") (pinfunction "A_1") (pintype "passive"))
      (node (ref "RF6") (pin "2") (pinfunction "2_2") (pintype "passive"))
    )
    (net (code "30") (name "Net-(DF7-A)") (class "Default")
      (node (ref "DF7") (pin "1") (pinfunction "A_1") (pintype "passive"))
      (node (ref "RF7") (pin "2") (pinfunction "2_2") (pintype "passive"))
    )
    (net (code "31") (name "Net-(DF8-A)") (class "Default")
      (node (ref "DF8") (pin "1") (pinfunction "A_1") (pintype "passive"))
      (node (ref "RF8") (pin "2") (pinfunction "2_2") (pintype "passive"))
    )
    (net (code "32") (name "Net-(DF9-A)") (class "Default")
      (node (ref "DF9") (pin "1") (pinfunction "A_1") (pintype "passive"))
      (node (ref "RF9") (pin "2") (pinfunction "2_2") (pintype "passive"))
    )
    (net (code "33") (name "Net-(DF10-A)") (class "Default")
      (node (ref "DF10") (pin "1") (pinfunction "A_1") (pintype "passive"))
      (node (ref "RF10") (pin "2") (pinfunction "2_2") (pintype "passive"))
    )
    (net (code "34") (name "Net-(DF11-A)") (class "Default")
      (node (ref "DF11") (pin "1") (pinfunction "A_1") (pintype "passive"))
      (node (ref "RF11") (pin "2") (pinfunction "2_2") (pintype "passive"))
    )
    (net (code "35") (name "Net-(DF12-A)") (class "Default")
      (node (ref "DF12") (pin "1") (pinfunction "A_1") (pintype "passive"))
      (node (ref "RF12") (pin "2") (pinfunction "2_2") (pintype "passive"))
    )
    (net (code "36") (name "Net-(DF13-A)") (class "Default")
      (node (ref "DF13") (pin "1") (pinfunction "A_1") (pintype "passive"))
      (node (ref "RF13") (pin "2") (pinfunction "2_2") (pintype "passive"))
    )
    (net (code "37") (name "Net-(DF14-A)") (class "Default")
      (node (ref "DF14") (pin "1") (pinfunction "A_1") (pintype "passive"))
      (node (ref "RF14") (pin "2") (pinfunction "2_2") (pintype "passive"))
    )
    (net (code "38") (name "Net-(DF15-A)") (class "Default")
      (node (ref "DF15") (pin "1") (pinfunction "A_1") (pintype "passive"))
      (node (ref "RF15") (pin "2") (pinfunction "2_2") (pintype "passive"))
    )
    (net (code "39") (name "Net-(DF16-A)") (class "Default")
      (node (ref "DF16") (pin "1") (pinfunction "A_1") (pintype "passive"))
      (node (ref "RF16") (pin "2") (pinfunction "2_2") (pintype "passive"))
    )
    (net (code "40") (name "Net-(DF17-A)") (class "Default")
      (node (ref "DF17") (pin "1") (pinfunction "A_1") (pintype "passive"))
      (node (ref "RF17") (pin "2") (pinfunction "2_2") (pintype "passive"))
    )
    (net (code "41") (name "Net-(DF18-A)") (class "Default")
      (node (ref "DF18") (pin "1") (pinfunction "A_1") (pintype "passive"))
      (node (ref "RF18") (pin "2") (pinfunction "2_2") (pintype "passive"))
    )
    (net (code "42") (name "Net-(DF19-A)") (class "Default")
      (node (ref "DF19") (pin "1") (pinfunction "A_1") (pintype "passive"))
      (node (ref "RF19") (pin "2") (pinfunction "2_2") (pintype "passive"))
    )
    (net (code "43") (name "Net-(DF20-A)") (class "Default")
      (node (ref "DF20") (pin "1") (pinfunction "A_1") (pintype "passive"))
      (node (ref "RF20") (pin "2") (pinfunction "2_2") (pintype "passive"))
    )
    (net (code "44") (name "Net-(DF21-A)") (class "Default")
      (node (ref "DF21") (pin "1") (pinfunction "A_1") (pintype "passive"))
      (node (ref "RF21") (pin "2") (pinfunction "2_2") (pintype "passive"))
    )
    (net (code "45") (name "Net-(DF22-A)") (class "Default")
      (node (ref "DF22") (pin "1") (pinfunction "A_1") (pintype "passive"))
      (node (ref "RF22") (pin "2") (pinfunction "2_2") (pintype "passive"))
    )
    (net (code "46") (name "Net-(DF23-A)") (class "Default")
      (node (ref "DF23") (pin "1") (pinfunction "A_1") (pintype "passive"))
      (node (ref "RF23") (pin "2") (pinfunction "2_2") (pintype "passive"))
    )
    (net (code "47") (name "Net-(DF24-A)") (class "Default")
      (node (ref "DF24") (pin "1") (pinfunction "A_1") (pintype "passive"))
      (node (ref "RF24") (pin "2") (pinfunction "2_2") (pintype "passive"))
    )
    (net (code "48") (name "Net-(DF25-A)") (class "Default")
      (node (ref "DF25") (pin "1") (pinfunction "A_1") (pintype "passive"))
      (node (ref "RF25") (pin "2") (pinfunction "2_2") (pintype "passive"))
    )
    (net (code "49") (name "Net-(DF26-A)") (class "Default")
      (node (ref "DF26") (pin "1") (pinfunction "A_1") (pintype "passive"))
      (node (ref "RF26") (pin "2") (pinfunction "2_2") (pintype "passive"))
    )
    (net (code "50") (name "Net-(DF27-A)") (class "Default")
      (node (ref "DF27") (pin "1") (pinfunction "A_1") (pintype "passive"))
      (node (ref "RF27") (pin "2") (pinfunction "2_2") (pintype "passive"))
    )
    (net (code "51") (name "Net-(DF28-A)") (class "Default")
      (node (ref "DF28") (pin "1") (pinfunction "A_1") (pintype "passive"))
      (node (ref "RF28") (pin "2") (pinfunction "2_2") (pintype "passive"))
    )
    (net (code "52") (name "Net-(DF29-A)") (class "Default")
      (node (ref "DF29") (pin "1") (pinfunction "A_1") (pintype "passive"))
      (node (ref "RF29") (pin "2") (pinfunction "2_2") (pintype "passive"))
    )
    (net (code "53") (name "Net-(DF30-A)") (class "Default")
      (node (ref "DF30") (pin "1") (pinfunction "A_1") (pintype "passive"))
      (node (ref "RF30") (pin "2") (pinfunction "2_2") (pintype "passive"))
    )
    (net (code "54") (name "Net-(DF31-A)") (class "Default")
      (node (ref "DF31") (pin "1") (pinfunction "A_1") (pintype "passive"))
      (node (ref "RF31") (pin "2") (pinfunction "2_2") (pintype "passive"))
    )
    (net (code "55") (name "Net-(DF32-A)") (class "Default")
      (node (ref "DF32") (pin "1") (pinfunction "A_1") (pintype "passive"))
      (node (ref "RF32") (pin "2") (pinfunction "2_2") (pintype "passive"))
    )
    (net (code "56") (name "Net-(DF33-A)") (class "Default")
      (node (ref "DF33") (pin "1") (pinfunction "A_1") (pintype "passive"))
      (node (ref "RF33") (pin "2") (pinfunction "2_2") (pintype "passive"))
    )
    (net (code "57") (name "Net-(DF34-A)") (class "Default")
      (node (ref "DF34") (pin "1") (pinfunction "A_1") (pintype "passive"))
      (node (ref "RF34") (pin "2") (pinfunction "2_2") (pintype "passive"))
    )
    (net (code "58") (name "Net-(DF35-A)") (class "Default")
      (node (ref "DF35") (pin "1") (pinfunction "A_1") (pintype "passive"))
      (node (ref "RF35") (pin "2") (pinfunction "2_2") (pintype "passive"))
    )
    (net (code "59") (name "Net-(DF36-A)") (class "Default")
      (node (ref "DF36") (pin "1") (pinfunction "A_1") (pintype "passive"))
      (node (ref "RF36") (pin "2") (pinfunction "2_2") (pintype "passive"))
    )
    (net (code "60") (name "Net-(DF37-A)") (class "Default")
      (node (ref "DF37") (pin "1") (pinfunction "A_1") (pintype "passive"))
      (node (ref "RF37") (pin "2") (pinfunction "2_2") (pintype "passive"))
    )
    (net (code "61") (name "Net-(DF38-A)") (class "Default")
      (node (ref "DF38") (pin "1") (pinfunction "A_1") (pintype "passive"))
      (node (ref "RF38") (pin "2") (pinfunction "2_2") (pintype "passive"))
    )
    (net (code "62") (name "Net-(DF39-A)") (class "Default")
      (node (ref "DF39") (pin "1") (pinfunction "A_1") (pintype "passive"))
      (node (ref "RF39") (pin "2") (pinfunction "2_2") (pintype "passive"))
    )
    (net (code "63") (name "Net-(DF40-A)") (class "Default")
      (node (ref "DF40") (pin "1") (pinfunction "A_1") (pintype "passive"))
      (node (ref "RF40") (pin "2") (pinfunction "2_2") (pintype "passive"))
    )
    (net (code "64") (name "Net-(DF41-A)") (class "Default")
      (node (ref "DF41") (pin "1") (pinfunction "A_1") (pintype "passive"))
      (node (ref "RF41") (pin "2") (pinfunction "2_2") (pintype "passive"))
    )
    (net (code "65") (name "Net-(DF42-A)") (class "Default")
      (node (ref "DF42") (pin "1") (pinfunction "A_1") (pintype "passive"))
      (node (ref "RF42") (pin "2") (pinfunction "2_2") (pintype "passive"))
    )
    (net (code "66") (name "Net-(DF43-A)") (class "Default")
      (node (ref "DF43") (pin "1") (pinfunction "A_1") (pintype "passive"))
      (node (ref "RF43") (pin "2") (pinfunction "2_2") (pintype "passive"))
    )
    (net (code "67") (name "Net-(DF44-A)") (class "Default")
      (node (ref "DF44") (pin "1") (pinfunction "A_1") (pintype "passive"))
      (node (ref "RF44") (pin "2") (pinfunction "2_2") (pintype "passive"))
    )
    (net (code "68") (name "Net-(DF45-A)") (class "Default")
      (node (ref "DF45") (pin "1") (pinfunction "A_1") (pintype "passive"))
      (node (ref "RF45") (pin "2") (pinfunction "2_2") (pintype "passive"))
    )
    (net (code "69") (name "Net-(DF46-A)") (class "Default")
      (node (ref "DF46") (pin "1") (pinfunction "A_1") (pintype "passive"))
      (node (ref "RF46") (pin "2") (pinfunction "2_2") (pintype "passive"))
    )
    (net (code "70") (name "Net-(DF47-A)") (class "Default")
      (node (ref "DF47") (pin "1") (pinfunction "A_1") (pintype "passive"))
      (node (ref "RF47") (pin "2") (pinfunction "2_2") (pintype "passive"))
    )
    (net (code "71") (name "Net-(DF48-A)") (class "Default")
      (node (ref "DF48") (pin "1") (pinfunction "A_1") (pintype "passive"))
      (node (ref "RF48") (pin "2") (pinfunction "2_2") (pintype "passive"))
    )
    (net (code "72") (name "Net-(DF49-A)") (class "Default")
      (node (ref "DF49") (pin "1") (pinfunction "A_1") (pintype "passive"))
      (node (ref "RF49") (pin "2") (pinfunction "2_2") (pintype "passive"))
    )
    (net (code "73") (name "Net-(DF50-A)") (class "Default")
      (node (ref "DF50") (pin "1") (pinfunction "A_1") (pintype "passive"))
      (node (ref "RF50") (pin "2") (pinfunction "2_2") (pintype "passive"))
    )
    (net (code "74") (name "Net-(DF51-A)") (class "Default")
      (node (ref "DF51") (pin "1") (pinfunction "A_1") (pintype "passive"))
      (node (ref "RF51") (pin "2") (pinfunction "2_2") (pintype "passive"))
    )
    (net (code "75") (name "Net-(DF52-A)") (class "Default")
      (node (ref "DF52") (pin "1") (pinfunction "A_1") (pintype "passive"))
      (node (ref "RF52") (pin "2") (pinfunction "2_2") (pintype "passive"))
    )
    (net (code "76") (name "Net-(DF53-A)") (class "Default")
      (node (ref "DF53") (pin "1") (pinfunction "A_1") (pintype "passive"))
      (node (ref "RF53") (pin "2") (pinfunction "2_2") (pintype "passive"))
    )
    (net (code "77") (name "Net-(DF54-A)") (class "Default")
      (node (ref "DF54") (pin "1") (pinfunction "A_1") (pintype "passive"))
      (node (ref "RF54") (pin "2") (pinfunction "2_2") (pintype "passive"))
    )
    (net (code "78") (name "Net-(DF55-A)") (class "Default")
      (node (ref "DF55") (pin "1") (pinfunction "A_1") (pintype "passive"))
      (node (ref "RF55") (pin "2") (pinfunction "2_2") (pintype "passive"))
    )
    (net (code "79") (name "Net-(DF56-A)") (class "Default")
      (node (ref "DF56") (pin "1") (pinfunction "A_1") (pintype "passive"))
      (node (ref "RF56") (pin "2") (pinfunction "2_2") (pintype "passive"))
    )
    (net (code "80") (name "Net-(DF57-A)") (class "Default")
      (node (ref "DF57") (pin "1") (pinfunction "A_1") (pintype "passive"))
      (node (ref "RF57") (pin "2") (pinfunction "2_2") (pintype "passive"))
    )
    (net (code "81") (name "Net-(DF58-A)") (class "Default")
      (node (ref "DF58") (pin "1") (pinfunction "A_1") (pintype "passive"))
      (node (ref "RF58") (pin "2") (pinfunction "2_2") (pintype "passive"))
    )
    (net (code "82") (name "Net-(DF59-A)") (class "Default")
      (node (ref "DF59") (pin "1") (pinfunction "A_1") (pintype "passive"))
      (node (ref "RF59") (pin "2") (pinfunction "2_2") (pintype "passive"))
    )
    (net (code "83") (name "Net-(DF60-A)") (class "Default")
      (node (ref "DF60") (pin "1") (pinfunction "A_1") (pintype "passive"))
      (node (ref "RF60") (pin "2") (pinfunction "2_2") (pintype "passive"))
    )
    (net (code "84") (name "Net-(DF61-A)") (class "Default")
      (node (ref "DF61") (pin "1") (pinfunction "A_1") (pintype "passive"))
      (node (ref "RF61") (pin "2") (pinfunction "2_2") (pintype "passive"))
    )
    (net (code "85") (name "Net-(DF62-A)") (class "Default")
      (node (ref "DF62") (pin "1") (pinfunction "A_1") (pintype "passive"))
      (node (ref "RF62") (pin "2") (pinfunction "2_2") (pintype "passive"))
    )
    (net (code "86") (name "Net-(DF63-A)") (class "Default")
      (node (ref "DF63") (pin "1") (pinfunction "A_1") (pintype "passive"))
      (node (ref "RF63") (pin "2") (pinfunction "2_2") (pintype "passive"))
    )
    (net (code "87") (name "Net-(DF64-A)") (class "Default")
      (node (ref "DF64") (pin "1") (pinfunction "A_1") (pintype "passive"))
      (node (ref "RF64") (pin "2") (pinfunction "2_2") (pintype "passive"))
    )
    (net (code "88") (name "Net-(DF65-A)") (class "Default")
      (node (ref "DF65") (pin "1") (pinfunction "A_1") (pintype "passive"))
      (node (ref "RF65") (pin "2") (pinfunction "2_2") (pintype "passive"))
    )
    (net (code "89") (name "Net-(DF66-A)") (class "Default")
      (node (ref "DF66") (pin "1") (pinfunction "A_1") (pintype "passive"))
      (node (ref "RF66") (pin "2") (pinfunction "2_2") (pintype "passive"))
    )
    (net (code "90") (name "Net-(DF67-A)") (class "Default")
      (node (ref "DF67") (pin "1") (pinfunction "A_1") (pintype "passive"))
      (node (ref "RF67") (pin "2") (pinfunction "2_2") (pintype "passive"))
    )
    (net (code "91") (name "Net-(DF68-A)") (class "Default")
      (node (ref "DF68") (pin "1") (pinfunction "A_1") (pintype "passive"))
      (node (ref "RF68") (pin "2") (pinfunction "2_2") (pintype "passive"))
    )
    (net (code "92") (name "Net-(DF69-A)") (class "Default")
      (node (ref "DF69") (pin "1") (pinfunction "A_1") (pintype "passive"))
      (node (ref "RF69") (pin "2") (pinfunction "2_2") (pintype "passive"))
    )
    (net (code "93") (name "Net-(DF70-A)") (class "Default")
      (node (ref "DF70") (pin "1") (pinfunction "A_1") (pintype "passive"))
      (node (ref "RF70") (pin "2") (pinfunction "2_2") (pintype "passive"))
    )
    (net (code "94") (name "Net-(DF71-A)") (class "Default")
      (node (ref "DF71") (pin "1") (pinfunction "A_1") (pintype "passive"))
      (node (ref "RF71") (pin "2") (pinfunction "2_2") (pintype "passive"))
    )
    (net (code "95") (name "Net-(DF72-A)") (class "Default")
      (node (ref "DF72") (pin "1") (pinfunction "A_1") (pintype "passive"))
      (node (ref "RF72") (pin "2") (pinfunction "2_2") (pintype "passive"))
    )
    (net (code "96") (name "Net-(DF73-A)") (class "Default")
      (node (ref "DF73") (pin "1") (pinfunction "A_1") (pintype "passive"))
      (node (ref "RF73") (pin "2") (pinfunction "2_2") (pintype "passive"))
    )
    (net (code "97") (name "Net-(DF74-A)") (class "Default")
      (node (ref "DF74") (pin "1") (pinfunction "A_1") (pintype "passive"))
      (node (ref "RF74") (pin "2") (pinfunction "2_2") (pintype "passive"))
    )
    (net (code "98") (name "Net-(DF75-A)") (class "Default")
      (node (ref "DF75") (pin "1") (pinfunction "A_1") (pintype "passive"))
      (node (ref "RF75") (pin "2") (pinfunction "2_2") (pintype "passive"))
    )
    (net (code "99") (name "Net-(DF76-A)") (class "Default")
      (node (ref "DF76") (pin "1") (pinfunction "A_1") (pintype "passive"))
      (node (ref "RF76") (pin "2") (pinfunction "2_2") (pintype "passive"))
    )
    (net (code "100") (name "Net-(DF77-A)") (class "Default")
      (node (ref "DF77") (pin "1") (pinfunction "A_1") (pintype "passive"))
      (node (ref "RF77") (pin "2") (pinfunction "2_2") (pintype "passive"))
    )
    (net (code "101") (name "Net-(DF78-A)") (class "Default")
      (node (ref "DF78") (pin "1") (pinfunction "A_1") (pintype "passive"))
      (node (ref "RF78") (pin "2") (pinfunction "2_2") (pintype "passive"))
    )
    (net (code "102") (name "Net-(DF79-A)") (class "Default")
      (node (ref "DF79") (pin "1") (pinfunction "A_1") (pintype "passive"))
      (node (ref "RF79") (pin "2") (pinfunction "2_2") (pintype "passive"))
    )
    (net (code "103") (name "Net-(DF80-A)") (class "Default")
      (node (ref "DF80") (pin "1") (pinfunction "A_1") (pintype "passive"))
      (node (ref "RF80") (pin "2") (pinfunction "2_2") (pintype "passive"))
    )
    (net (code "104") (name "Net-(DF81-A)") (class "Default")
      (node (ref "DF81") (pin "1") (pinfunction "A_1") (pintype "passive"))
      (node (ref "RF81") (pin "2") (pinfunction "2_2") (pintype "passive"))
    )
    (net (code "105") (name "Net-(DF82-A)") (class "Default")
      (node (ref "DF82") (pin "1") (pinfunction "A_1") (pintype "passive"))
      (node (ref "RF82") (pin "2") (pinfunction "2_2") (pintype "passive"))
    )
    (net (code "106") (name "Net-(DF83-A)") (class "Default")
      (node (ref "DF83") (pin "1") (pinfunction "A_1") (pintype "passive"))
      (node (ref "RF83") (pin "2") (pinfunction "2_2") (pintype "passive"))
    )
    (net (code "107") (name "Net-(DF84-A)") (class "Default")
      (node (ref "DF84") (pin "1") (pinfunction "A_1") (pintype "passive"))
      (node (ref "RF84") (pin "2") (pinfunction "2_2") (pintype "passive"))
    )
    (net (code "108") (name "Net-(DF85-A)") (class "Default")
      (node (ref "DF85") (pin "1") (pinfunction "A_1") (pintype "passive"))
      (node (ref "RF85") (pin "2") (pinfunction "2_2") (pintype "passive"))
    )
    (net (code "109") (name "Net-(DF86-A)") (class "Default")
      (node (ref "DF86") (pin "1") (pinfunction "A_1") (pintype "passive"))
      (node (ref "RF86") (pin "2") (pinfunction "2_2") (pintype "passive"))
    )
    (net (code "110") (name "Net-(DF87-A)") (class "Default")
      (node (ref "DF87") (pin "1") (pinfunction "A_1") (pintype "passive"))
      (node (ref "RF87") (pin "2") (pinfunction "2_2") (pintype "passive"))
    )
    (net (code "111") (name "Net-(DF88-A)") (class "Default")
      (node (ref "DF88") (pin "1") (pinfunction "A_1") (pintype "passive"))
      (node (ref "RF88") (pin "2") (pinfunction "2_2") (pintype "passive"))
    )
    (net (code "112") (name "Net-(DF89-A)") (class "Default")
      (node (ref "DF89") (pin "1") (pinfunction "A_1") (pintype "passive"))
      (node (ref "RF89") (pin "2") (pinfunction "2_2") (pintype "passive"))
    )
    (net (code "113") (name "Net-(DF90-A)") (class "Default")
      (node (ref "DF90") (pin "1") (pinfunction "A_1") (pintype "passive"))
      (node (ref "RF90") (pin "2") (pinfunction "2_2") (pintype "passive"))
    )
    (net (code "114") (name "Net-(DF91-A)") (class "Default")
      (node (ref "DF91") (pin "1") (pinfunction "A_1") (pintype "passive"))
      (node (ref "RF91") (pin "2") (pinfunction "2_2") (pintype "passive"))
    )
    (net (code "115") (name "Net-(DF92-A)") (class "Default")
      (node (ref "DF92") (pin "1") (pinfunction "A_1") (pintype "passive"))
      (node (ref "RF92") (pin "2") (pinfunction "2_2") (pintype "passive"))
    )
    (net (code "116") (name "Net-(DF93-A)") (class "Default")
      (node (ref "DF93") (pin "1") (pinfunction "A_1") (pintype "passive"))
      (node (ref "RF93") (pin "2") (pinfunction "2_2") (pintype "passive"))
    )
    (net (code "117") (name "Net-(DF94-A)") (class "Default")
      (node (ref "DF94") (pin "1") (pinfunction "A_1") (pintype "passive"))
      (node (ref "RF94") (pin "2") (pinfunction "2_2") (pintype "passive"))
    )
    (net (code "118") (name "Net-(DF95-A)") (class "Default")
      (node (ref "DF95") (pin "1") (pinfunction "A_1") (pintype "passive"))
      (node (ref "RF95") (pin "2") (pinfunction "2_2") (pintype "passive"))
    )
    (net (code "119") (name "Net-(DF96-A)") (class "Default")
      (node (ref "DF96") (pin "1") (pinfunction "A_1") (pintype "passive"))
      (node (ref "RF96") (pin "2") (pinfunction "2_2") (pintype "passive"))
    )
    (net (code "120") (name "Net-(DF97-A)") (class "Default")
      (node (ref "DF97") (pin "1") (pinfunction "A_1") (pintype "passive"))
      (node (ref "RF97") (pin "2") (pinfunction "2_2") (pintype "passive"))
    )
    (net (code "121") (name "Net-(DF98-A)") (class "Default")
      (node (ref "DF98") (pin "1") (pinfunction "A_1") (pintype "passive"))
      (node (ref "RF98") (pin "2") (pinfunction "2_2") (pintype "passive"))
    )
    (net (code "122") (name "Net-(DF99-A)") (class "Default")
      (node (ref "DF99") (pin "1") (pinfunction "A_1") (pintype "passive"))
      (node (ref "RF99") (pin "2") (pinfunction "2_2") (pintype "passive"))
    )
    (net (code "123") (name "Net-(DF100-A)") (class "Default")
      (node (ref "DF100") (pin "1") (pinfunction "A_1") (pintype "passive"))
      (node (ref "RF100") (pin "2") (pinfunction "2_2") (pintype "passive"))
    )
    (net (code "124") (name "Net-(DF101-A)") (class "Default")
      (node (ref "DF101") (pin "1") (pinfunction "A_1") (pintype "passive"))
      (node (ref "RF101") (pin "2") (pinfunction "2_2") (pintype "passive"))
    )
    (net (code "125") (name "Net-(DF102-A)") (class "Default")
      (node (ref "DF102") (pin "1") (pinfunction "A_1") (pintype "passive"))
      (node (ref "RF102") (pin "2") (pinfunction "2_2") (pintype "passive"))
    )
    (net (code "126") (name "Net-(DF103-A)") (class "Default")
      (node (ref "DF103") (pin "1") (pinfunction "A_1") (pintype "passive"))
      (node (ref "RF103") (pin "2") (pinfunction "2_2") (pintype "passive"))
    )
    (net (code "127") (name "Net-(DF104-A)") (class "Default")
      (node (ref "DF104") (pin "1") (pinfunction "A_1") (pintype "passive"))
      (node (ref "RF104") (pin "2") (pinfunction "2_2") (pintype "passive"))
    )
    (net (code "128") (name "Net-(DF105-A)") (class "Default")
      (node (ref "DF105") (pin "1") (pinfunction "A_1") (pintype "passive"))
      (node (ref "RF105") (pin "2") (pinfunction "2_2") (pintype "passive"))
    )
    (net (code "129") (name "Net-(DF106-A)") (class "Default")
      (node (ref "DF106") (pin "1") (pinfunction "A_1") (pintype "passive"))
      (node (ref "RF106") (pin "2") (pinfunction "2_2") (pintype "passive"))
    )
    (net (code "130") (name "Net-(DF107-A)") (class "Default")
      (node (ref "DF107") (pin "1") (pinfunction "A_1") (pintype "passive"))
      (node (ref "RF107") (pin "2") (pinfunction "2_2") (pintype "passive"))
    )
    (net (code "131") (name "Net-(DF108-A)") (class "Default")
      (node (ref "DF108") (pin "1") (pinfunction "A_1") (pintype "passive"))
      (node (ref "RF108") (pin "2") (pinfunction "2_2") (pintype "passive"))
    )
    (net (code "132") (name "Net-(DF109-A)") (class "Default")
      (node (ref "DF109") (pin "1") (pinfunction "A_1") (pintype "passive"))
      (node (ref "RF109") (pin "2") (pinfunction "2_2") (pintype "passive"))
    )
    (net (code "133") (name "Net-(DF110-A)") (class "Default")
      (node (ref "DF110") (pin "1") (pinfunction "A_1") (pintype "passive"))
      (node (ref "RF110") (pin "2") (pinfunction "2_2") (pintype "passive"))
    )
    (net (code "134") (name "Net-(DF111-A)") (class "Default")
      (node (ref "DF111") (pin "1") (pinfunction "A_1") (pintype "passive"))
      (node (ref "RF111") (pin "2") (pinfunction "2_2") (pintype "passive"))
    )
    (net (code "135") (name "Net-(DF112-A)") (class "Default")
      (node (ref "DF112") (pin "1") (pinfunction "A_1") (pintype "passive"))
      (node (ref "RF112") (pin "2") (pinfunction "2_2") (pintype "passive"))
    )
    (net (code "136") (name "Net-(DF113-A)") (class "Default")
      (node (ref "DF113") (pin "1") (pinfunction "A_1") (pintype "passive"))
      (node (ref "RF113") (pin "2") (pinfunction "2_2") (pintype "passive"))
    )
    (net (code "137") (name "Net-(DF114-A)") (class "Default")
      (node (ref "DF114") (pin "1") (pinfunction "A_1") (pintype "passive"))
      (node (ref "RF114") (pin "2") (pinfunction "2_2") (pintype "passive"))
    )
    (net (code "138") (name "Net-(DF115-A)") (class "Default")
      (node (ref "DF115") (pin "1") (pinfunction "A_1") (pintype "passive"))
      (node (ref "RF115") (pin "2") (pinfunction "2_2") (pintype "passive"))
    )
    (net (code "139") (name "Net-(DF116-A)") (class "Default")
      (node (ref "DF116") (pin "1") (pinfunction "A_1") (pintype "passive"))
      (node (ref "RF116") (pin "2") (pinfunction "2_2") (pintype "passive"))
    )
    (net (code "140") (name "Net-(DF117-A)") (class "Default")
      (node (ref "DF117") (pin "1") (pinfunction "A_1") (pintype "passive"))
      (node (ref "RF117") (pin "2") (pinfunction "2_2") (pintype "passive"))
    )
    (net (code "141") (name "Net-(DF118-A)") (class "Default")
      (node (ref "DF118") (pin "1") (pinfunction "A_1") (pintype "passive"))
      (node (ref "RF118") (pin "2") (pinfunction "2_2") (pintype "passive"))
    )
    (net (code "142") (name "Net-(DF119-A)") (class "Default")
      (node (ref "DF119") (pin "1") (pinfunction "A_1") (pintype "passive"))
      (node (ref "RF119") (pin "2") (pinfunction "2_2") (pintype "passive"))
    )
    (net (code "143") (name "Net-(DF120-A)") (class "Default")
      (node (ref "DF120") (pin "1") (pinfunction "A_1") (pintype "passive"))
      (node (ref "RF120") (pin "2") (pinfunction "2_2") (pintype "passive"))
    )
    (net (code "144") (name "Net-(DF121-A)") (class "Default")
      (node (ref "DF121") (pin "1") (pinfunction "A_1") (pintype "passive"))
      (node (ref "RF121") (pin "2") (pinfunction "2_2") (pintype "passive"))
    )
    (net (code "145") (name "Net-(DF122-A)") (class "Default")
      (node (ref "DF122") (pin "1") (pinfunction "A_1") (pintype "passive"))
      (node (ref "RF122") (pin "2") (pinfunction "2_2") (pintype "passive"))
    )
    (net (code "146") (name "Net-(DF123-A)") (class "Default")
      (node (ref "DF123") (pin "1") (pinfunction "A_1") (pintype "passive"))
      (node (ref "RF123") (pin "2") (pinfunction "2_2") (pintype "passive"))
    )
    (net (code "147") (name "Net-(DF124-A)") (class "Default")
      (node (ref "DF124") (pin "1") (pinfunction "A_1") (pintype "passive"))
      (node (ref "RF124") (pin "2") (pinfunction "2_2") (pintype "passive"))
    )
    (net (code "148") (name "Net-(DF125-A)") (class "Default")
      (node (ref "DF125") (pin "1") (pinfunction "A_1") (pintype "passive"))
      (node (ref "RF125") (pin "2") (pinfunction "2_2") (pintype "passive"))
    )
    (net (code "149") (name "Net-(DF126-A)") (class "Default")
      (node (ref "DF126") (pin "1") (pinfunction "A_1") (pintype "passive"))
      (node (ref "RF126") (pin "2") (pinfunction "2_2") (pintype "passive"))
    )
    (net (code "150") (name "Net-(DF127-A)") (class "Default")
      (node (ref "DF127") (pin "1") (pinfunction "A_1") (pintype "passive"))
      (node (ref "RF127") (pin "2") (pinfunction "2_2") (pintype "passive"))
    )
    (net (code "151") (name "Net-(DF128-A)") (class "Default")
      (node (ref "DF128") (pin "1") (pinfunction "A_1") (pintype "passive"))
      (node (ref "RF128") (pin "2") (pinfunction "2_2") (pintype "passive"))
    )
    (net (code "152") (name "Net-(UF1-QA)") (class "Default")
      (node (ref "RF8") (pin "1") (pinfunction "1_1") (pintype "passive"))
      (node (ref "UF1") (pin "15") (pinfunction "QA_15") (pintype "tri_state"))
    )
    (net (code "153") (name "Net-(UF1-QB)") (class "Default")
      (node (ref "RF7") (pin "1") (pinfunction "1_1") (pintype "passive"))
      (node (ref "UF1") (pin "1") (pinfunction "QB_1") (pintype "tri_state"))
    )
    (net (code "154") (name "Net-(UF1-QC)") (class "Default")
      (node (ref "RF6") (pin "1") (pinfunction "1_1") (pintype "passive"))
      (node (ref "UF1") (pin "2") (pinfunction "QC_2") (pintype "tri_state"))
    )
    (net (code "155") (name "Net-(UF1-QD)") (class "Default")
      (node (ref "RF5") (pin "1") (pinfunction "1_1") (pintype "passive"))
      (node (ref "UF1") (pin "3") (pinfunction "QD_3") (pintype "tri_state"))
    )
    (net (code "156") (name "Net-(UF1-QE)") (class "Default")
      (node (ref "RF4") (pin "1") (pinfunction "1_1") (pintype "passive"))
      (node (ref "UF1") (pin "4") (pinfunction "QE_4") (pintype "tri_state"))
    )
    (net (code "157") (name "Net-(UF1-QF)") (class "Default")
      (node (ref "RF3") (pin "1") (pinfunction "1_1") (pintype "passive"))
      (node (ref "UF1") (pin "5") (pinfunction "QF_5") (pintype "tri_state"))
    )
    (net (code "158") (name "Net-(UF1-QG)") (class "Default")
      (node (ref "RF2") (pin "1") (pinfunction "1_1") (pintype "passive"))
      (node (ref "UF1") (pin "6") (pinfunction "QG_6") (pintype "tri_state"))
    )
    (net (code "159") (name "Net-(UF1-QH)") (class "Default")
      (node (ref "RF1") (pin "1") (pinfunction "1_1") (pintype "passive"))
      (node (ref "UF1") (pin "7") (pinfunction "QH_7") (pintype "tri_state"))
    )
    (net (code "160") (name "Net-(UF2-QA)") (class "Default")
      (node (ref "RF16") (pin "1") (pinfunction "1_1") (pintype "passive"))
      (node (ref "UF2") (pin "15") (pinfunction "QA_15") (pintype "tri_state"))
    )
    (net (code "161") (name "Net-(UF2-QB)") (class "Default")
      (node (ref "RF15") (pin "1") (pinfunction "1_1") (pintype "passive"))
      (node (ref "UF2") (pin "1") (pinfunction "QB_1") (pintype "tri_state"))
    )
    (net (code "162") (name "Net-(UF2-QC)") (class "Default")
      (node (ref "RF14") (pin "1") (pinfunction "1_1") (pintype "passive"))
      (node (ref "UF2") (pin "2") (pinfunction "QC_2") (pintype "tri_state"))
    )
    (net (code "163") (name "Net-(UF2-QD)") (class "Default")
      (node (ref "RF13") (pin "1") (pinfunction "1_1") (pintype "passive"))
      (node (ref "UF2") (pin "3") (pinfunction "QD_3") (pintype "tri_state"))
    )
    (net (code "164") (name "Net-(UF2-QE)") (class "Default")
      (node (ref "RF12") (pin "1") (pinfunction "1_1") (pintype "passive"))
      (node (ref "UF2") (pin "4") (pinfunction "QE_4") (pintype "tri_state"))
    )
    (net (code "165") (name "Net-(UF2-QF)") (class "Default")
      (node (ref "RF11") (pin "1") (pinfunction "1_1") (pintype "passive"))
      (node (ref "UF2") (pin "5") (pinfunction "QF_5") (pintype "tri_state"))
    )
    (net (code "166") (name "Net-(UF2-QG)") (class "Default")
      (node (ref "RF10") (pin "1") (pinfunction "1_1") (pintype "passive"))
      (node (ref "UF2") (pin "6") (pinfunction "QG_6") (pintype "tri_state"))
    )
    (net (code "167") (name "Net-(UF2-QH)") (class "Default")
      (node (ref "RF9") (pin "1") (pinfunction "1_1") (pintype "passive"))
      (node (ref "UF2") (pin "7") (pinfunction "QH_7") (pintype "tri_state"))
    )
    (net (code "168") (name "Net-(UF3-QA)") (class "Default")
      (node (ref "RF24") (pin "1") (pinfunction "1_1") (pintype "passive"))
      (node (ref "UF3") (pin "15") (pinfunction "QA_15") (pintype "tri_state"))
    )
    (net (code "169") (name "Net-(UF3-QB)") (class "Default")
      (node (ref "RF23") (pin "1") (pinfunction "1_1") (pintype "passive"))
      (node (ref "UF3") (pin "1") (pinfunction "QB_1") (pintype "tri_state"))
    )
    (net (code "170") (name "Net-(UF3-QC)") (class "Default")
      (node (ref "RF22") (pin "1") (pinfunction "1_1") (pintype "passive"))
      (node (ref "UF3") (pin "2") (pinfunction "QC_2") (pintype "tri_state"))
    )
    (net (code "171") (name "Net-(UF3-QD)") (class "Default")
      (node (ref "RF21") (pin "1") (pinfunction "1_1") (pintype "passive"))
      (node (ref "UF3") (pin "3") (pinfunction "QD_3") (pintype "tri_state"))
    )
    (net (code "172") (name "Net-(UF3-QE)") (class "Default")
      (node (ref "RF20") (pin "1") (pinfunction "1_1") (pintype "passive"))
      (node (ref "UF3") (pin "4") (pinfunction "QE_4") (pintype "tri_state"))
    )
    (net (code "173") (name "Net-(UF3-QF)") (class "Default")
      (node (ref "RF19") (pin "1") (pinfunction "1_1") (pintype "passive"))
      (node (ref "UF3") (pin "5") (pinfunction "QF_5") (pintype "tri_state"))
    )
    (net (code "174") (name "Net-(UF3-QG)") (class "Default")
      (node (ref "RF18") (pin "1") (pinfunction "1_1") (pintype "passive"))
      (node (ref "UF3") (pin "6") (pinfunction "QG_6") (pintype "tri_state"))
    )
    (net (code "175") (name "Net-(UF3-QH)") (class "Default")
      (node (ref "RF17") (pin "1") (pinfunction "1_1") (pintype "passive"))
      (node (ref "UF3") (pin "7") (pinfunction "QH_7") (pintype "tri_state"))
    )
    (net (code "176") (name "Net-(UF4-QA)") (class "Default")
      (node (ref "RF32") (pin "1") (pinfunction "1_1") (pintype "passive"))
      (node (ref "UF4") (pin "15") (pinfunction "QA_15") (pintype "tri_state"))
    )
    (net (code "177") (name "Net-(UF4-QB)") (class "Default")
      (node (ref "RF31") (pin "1") (pinfunction "1_1") (pintype "passive"))
      (node (ref "UF4") (pin "1") (pinfunction "QB_1") (pintype "tri_state"))
    )
    (net (code "178") (name "Net-(UF4-QC)") (class "Default")
      (node (ref "RF30") (pin "1") (pinfunction "1_1") (pintype "passive"))
      (node (ref "UF4") (pin "2") (pinfunction "QC_2") (pintype "tri_state"))
    )
    (net (code "179") (name "Net-(UF4-QD)") (class "Default")
      (node (ref "RF29") (pin "1") (pinfunction "1_1") (pintype "passive"))
      (node (ref "UF4") (pin "3") (pinfunction "QD_3") (pintype "tri_state"))
    )
    (net (code "180") (name "Net-(UF4-QE)") (class "Default")
      (node (ref "RF28") (pin "1") (pinfunction "1_1") (pintype "passive"))
      (node (ref "UF4") (pin "4") (pinfunction "QE_4") (pintype "tri_state"))
    )
    (net (code "181") (name "Net-(UF4-QF)") (class "Default")
      (node (ref "RF27") (pin "1") (pinfunction "1_1") (pintype "passive"))
      (node (ref "UF4") (pin "5") (pinfunction "QF_5") (pintype "tri_state"))
    )
    (net (code "182") (name "Net-(UF4-QG)") (class "Default")
      (node (ref "RF26") (pin "1") (pinfunction "1_1") (pintype "passive"))
      (node (ref "UF4") (pin "6") (pinfunction "QG_6") (pintype "tri_state"))
    )
    (net (code "183") (name "Net-(UF4-QH)") (class "Default")
      (node (ref "RF25") (pin "1") (pinfunction "1_1") (pintype "passive"))
      (node (ref "UF4") (pin "7") (pinfunction "QH_7") (pintype "tri_state"))
    )
    (net (code "184") (name "Net-(UF5-QA)") (class "Default")
      (node (ref "RF40") (pin "1") (pinfunction "1_1") (pintype "passive"))
      (node (ref "UF5") (pin "15") (pinfunction "QA_15") (pintype "tri_state"))
    )
    (net (code "185") (name "Net-(UF5-QB)") (class "Default")
      (node (ref "RF39") (pin "1") (pinfunction "1_1") (pintype "passive"))
      (node (ref "UF5") (pin "1") (pinfunction "QB_1") (pintype "tri_state"))
    )
    (net (code "186") (name "Net-(UF5-QC)") (class "Default")
      (node (ref "RF38") (pin "1") (pinfunction "1_1") (pintype "passive"))
      (node (ref "UF5") (pin "2") (pinfunction "QC_2") (pintype "tri_state"))
    )
    (net (code "187") (name "Net-(UF5-QD)") (class "Default")
      (node (ref "RF37") (pin "1") (pinfunction "1_1") (pintype "passive"))
      (node (ref "UF5") (pin "3") (pinfunction "QD_3") (pintype "tri_state"))
    )
    (net (code "188") (name "Net-(UF5-QE)") (class "Default")
      (node (ref "RF36") (pin "1") (pinfunction "1_1") (pintype "passive"))
      (node (ref "UF5") (pin "4") (pinfunction "QE_4") (pintype "tri_state"))
    )
    (net (code "189") (name "Net-(UF5-QF)") (class "Default")
      (node (ref "RF35") (pin "1") (pinfunction "1_1") (pintype "passive"))
      (node (ref "UF5") (pin "5") (pinfunction "QF_5") (pintype "tri_state"))
    )
    (net (code "190") (name "Net-(UF5-QG)") (class "Default")
      (node (ref "RF34") (pin "1") (pinfunction "1_1") (pintype "passive"))
      (node (ref "UF5") (pin "6") (pinfunction "QG_6") (pintype "tri_state"))
    )
    (net (code "191") (name "Net-(UF5-QH)") (class "Default")
      (node (ref "RF33") (pin "1") (pinfunction "1_1") (pintype "passive"))
      (node (ref "UF5") (pin "7") (pinfunction "QH_7") (pintype "tri_state"))
    )
    (net (code "192") (name "Net-(UF6-QA)") (class "Default")
      (node (ref "RF48") (pin "1") (pinfunction "1_1") (pintype "passive"))
      (node (ref "UF6") (pin "15") (pinfunction "QA_15") (pintype "tri_state"))
    )
    (net (code "193") (name "Net-(UF6-QB)") (class "Default")
      (node (ref "RF47") (pin "1") (pinfunction "1_1") (pintype "passive"))
      (node (ref "UF6") (pin "1") (pinfunction "QB_1") (pintype "tri_state"))
    )
    (net (code "194") (name "Net-(UF6-QC)") (class "Default")
      (node (ref "RF46") (pin "1") (pinfunction "1_1") (pintype "passive"))
      (node (ref "UF6") (pin "2") (pinfunction "QC_2") (pintype "tri_state"))
    )
    (net (code "195") (name "Net-(UF6-QD)") (class "Default")
      (node (ref "RF45") (pin "1") (pinfunction "1_1") (pintype "passive"))
      (node (ref "UF6") (pin "3") (pinfunction "QD_3") (pintype "tri_state"))
    )
    (net (code "196") (name "Net-(UF6-QE)") (class "Default")
      (node (ref "RF44") (pin "1") (pinfunction "1_1") (pintype "passive"))
      (node (ref "UF6") (pin "4") (pinfunction "QE_4") (pintype "tri_state"))
    )
    (net (code "197") (name "Net-(UF6-QF)") (class "Default")
      (node (ref "RF43") (pin "1") (pinfunction "1_1") (pintype "passive"))
      (node (ref "UF6") (pin "5") (pinfunction "QF_5") (pintype "tri_state"))
    )
    (net (code "198") (name "Net-(UF6-QG)") (class "Default")
      (node (ref "RF42") (pin "1") (pinfunction "1_1") (pintype "passive"))
      (node (ref "UF6") (pin "6") (pinfunction "QG_6") (pintype "tri_state"))
    )
    (net (code "199") (name "Net-(UF6-QH)") (class "Default")
      (node (ref "RF41") (pin "1") (pinfunction "1_1") (pintype "passive"))
      (node (ref "UF6") (pin "7") (pinfunction "QH_7") (pintype "tri_state"))
    )
    (net (code "200") (name "Net-(UF7-QA)") (class "Default")
      (node (ref "RF56") (pin "1") (pinfunction "1_1") (pintype "passive"))
      (node (ref "UF7") (pin "15") (pinfunction "QA_15") (pintype "tri_state"))
    )
    (net (code "201") (name "Net-(UF7-QB)") (class "Default")
      (node (ref "RF55") (pin "1") (pinfunction "1_1") (pintype "passive"))
      (node (ref "UF7") (pin "1") (pinfunction "QB_1") (pintype "tri_state"))
    )
    (net (code "202") (name "Net-(UF7-QC)") (class "Default")
      (node (ref "RF54") (pin "1") (pinfunction "1_1") (pintype "passive"))
      (node (ref "UF7") (pin "2") (pinfunction "QC_2") (pintype "tri_state"))
    )
    (net (code "203") (name "Net-(UF7-QD)") (class "Default")
      (node (ref "RF53") (pin "1") (pinfunction "1_1") (pintype "passive"))
      (node (ref "UF7") (pin "3") (pinfunction "QD_3") (pintype "tri_state"))
    )
    (net (code "204") (name "Net-(UF7-QE)") (class "Default")
      (node (ref "RF52") (pin "1") (pinfunction "1_1") (pintype "passive"))
      (node (ref "UF7") (pin "4") (pinfunction "QE_4") (pintype "tri_state"))
    )
    (net (code "205") (name "Net-(UF7-QF)") (class "Default")
      (node (ref "RF51") (pin "1") (pinfunction "1_1") (pintype "passive"))
      (node (ref "UF7") (pin "5") (pinfunction "QF_5") (pintype "tri_state"))
    )
    (net (code "206") (name "Net-(UF7-QG)") (class "Default")
      (node (ref "RF50") (pin "1") (pinfunction "1_1") (pintype "passive"))
      (node (ref "UF7") (pin "6") (pinfunction "QG_6") (pintype "tri_state"))
    )
    (net (code "207") (name "Net-(UF7-QH)") (class "Default")
      (node (ref "RF49") (pin "1") (pinfunction "1_1") (pintype "passive"))
      (node (ref "UF7") (pin "7") (pinfunction "QH_7") (pintype "tri_state"))
    )
    (net (code "208") (name "Net-(UF8-QA)") (class "Default")
      (node (ref "RF64") (pin "1") (pinfunction "1_1") (pintype "passive"))
      (node (ref "UF8") (pin "15") (pinfunction "QA_15") (pintype "tri_state"))
    )
    (net (code "209") (name "Net-(UF8-QB)") (class "Default")
      (node (ref "RF63") (pin "1") (pinfunction "1_1") (pintype "passive"))
      (node (ref "UF8") (pin "1") (pinfunction "QB_1") (pintype "tri_state"))
    )
    (net (code "210") (name "Net-(UF8-QC)") (class "Default")
      (node (ref "RF62") (pin "1") (pinfunction "1_1") (pintype "passive"))
      (node (ref "UF8") (pin "2") (pinfunction "QC_2") (pintype "tri_state"))
    )
    (net (code "211") (name "Net-(UF8-QD)") (class "Default")
      (node (ref "RF61") (pin "1") (pinfunction "1_1") (pintype "passive"))
      (node (ref "UF8") (pin "3") (pinfunction "QD_3") (pintype "tri_state"))
    )
    (net (code "212") (name "Net-(UF8-QE)") (class "Default")
      (node (ref "RF60") (pin "1") (pinfunction "1_1") (pintype "passive"))
      (node (ref "UF8") (pin "4") (pinfunction "QE_4") (pintype "tri_state"))
    )
    (net (code "213") (name "Net-(UF8-QF)") (class "Default")
      (node (ref "RF59") (pin "1") (pinfunction "1_1") (pintype "passive"))
      (node (ref "UF8") (pin "5") (pinfunction "QF_5") (pintype "tri_state"))
    )
    (net (code "214") (name "Net-(UF8-QG)") (class "Default")
      (node (ref "RF58") (pin "1") (pinfunction "1_1") (pintype "passive"))
      (node (ref "UF8") (pin "6") (pinfunction "QG_6") (pintype "tri_state"))
    )
    (net (code "215") (name "Net-(UF8-QH)") (class "Default")
      (node (ref "RF57") (pin "1") (pinfunction "1_1") (pintype "passive"))
      (node (ref "UF8") (pin "7") (pinfunction "QH_7") (pintype "tri_state"))
    )
    (net (code "216") (name "Net-(UF9-QA)") (class "Default")
      (node (ref "RF72") (pin "1") (pinfunction "1_1") (pintype "passive"))
      (node (ref "UF9") (pin "15") (pinfunction "QA_15") (pintype "tri_state"))
    )
    (net (code "217") (name "Net-(UF9-QB)") (class "Default")
      (node (ref "RF71") (pin "1") (pinfunction "1_1") (pintype "passive"))
      (node (ref "UF9") (pin "1") (pinfunction "QB_1") (pintype "tri_state"))
    )
    (net (code "218") (name "Net-(UF9-QC)") (class "Default")
      (node (ref "RF70") (pin "1") (pinfunction "1_1") (pintype "passive"))
      (node (ref "UF9") (pin "2") (pinfunction "QC_2") (pintype "tri_state"))
    )
    (net (code "219") (name "Net-(UF9-QD)") (class "Default")
      (node (ref "RF69") (pin "1") (pinfunction "1_1") (pintype "passive"))
      (node (ref "UF9") (pin "3") (pinfunction "QD_3") (pintype "tri_state"))
    )
    (net (code "220") (name "Net-(UF9-QE)") (class "Default")
      (node (ref "RF68") (pin "1") (pinfunction "1_1") (pintype "passive"))
      (node (ref "UF9") (pin "4") (pinfunction "QE_4") (pintype "tri_state"))
    )
    (net (code "221") (name "Net-(UF9-QF)") (class "Default")
      (node (ref "RF67") (pin "1") (pinfunction "1_1") (pintype "passive"))
      (node (ref "UF9") (pin "5") (pinfunction "QF_5") (pintype "tri_state"))
    )
    (net (code "222") (name "Net-(UF9-QG)") (class "Default")
      (node (ref "RF66") (pin "1") (pinfunction "1_1") (pintype "passive"))
      (node (ref "UF9") (pin "6") (pinfunction "QG_6") (pintype "tri_state"))
    )
    (net (code "223") (name "Net-(UF9-QH)") (class "Default")
      (node (ref "RF65") (pin "1") (pinfunction "1_1") (pintype "passive"))
      (node (ref "UF9") (pin "7") (pinfunction "QH_7") (pintype "tri_state"))
    )
    (net (code "224") (name "Net-(UF10-QA)") (class "Default")
      (node (ref "RF80") (pin "1") (pinfunction "1_1") (pintype "passive"))
      (node (ref "UF10") (pin "15") (pinfunction "QA_15") (pintype "tri_state"))
    )
    (net (code "225") (name "Net-(UF10-QB)") (class "Default")
      (node (ref "RF79") (pin "1") (pinfunction "1_1") (pintype "passive"))
      (node (ref "UF10") (pin "1") (pinfunction "QB_1") (pintype "tri_state"))
    )
    (net (code "226") (name "Net-(UF10-QC)") (class "Default")
      (node (ref "RF78") (pin "1") (pinfunction "1_1") (pintype "passive"))
      (node (ref "UF10") (pin "2") (pinfunction "QC_2") (pintype "tri_state"))
    )
    (net (code "227") (name "Net-(UF10-QD)") (class "Default")
      (node (ref "RF77") (pin "1") (pinfunction "1_1") (pintype "passive"))
      (node (ref "UF10") (pin "3") (pinfunction "QD_3") (pintype "tri_state"))
    )
    (net (code "228") (name "Net-(UF10-QE)") (class "Default")
      (node (ref "RF76") (pin "1") (pinfunction "1_1") (pintype "passive"))
      (node (ref "UF10") (pin "4") (pinfunction "QE_4") (pintype "tri_state"))
    )
    (net (code "229") (name "Net-(UF10-QF)") (class "Default")
      (node (ref "RF75") (pin "1") (pinfunction "1_1") (pintype "passive"))
      (node (ref "UF10") (pin "5") (pinfunction "QF_5") (pintype "tri_state"))
    )
    (net (code "230") (name "Net-(UF10-QG)") (class "Default")
      (node (ref "RF74") (pin "1") (pinfunction "1_1") (pintype "passive"))
      (node (ref "UF10") (pin "6") (pinfunction "QG_6") (pintype "tri_state"))
    )
    (net (code "231") (name "Net-(UF10-QH)") (class "Default")
      (node (ref "RF73") (pin "1") (pinfunction "1_1") (pintype "passive"))
      (node (ref "UF10") (pin "7") (pinfunction "QH_7") (pintype "tri_state"))
    )
    (net (code "232") (name "Net-(UF11-QA)") (class "Default")
      (node (ref "RF88") (pin "1") (pinfunction "1_1") (pintype "passive"))
      (node (ref "UF11") (pin "15") (pinfunction "QA_15") (pintype "tri_state"))
    )
    (net (code "233") (name "Net-(UF11-QB)") (class "Default")
      (node (ref "RF87") (pin "1") (pinfunction "1_1") (pintype "passive"))
      (node (ref "UF11") (pin "1") (pinfunction "QB_1") (pintype "tri_state"))
    )
    (net (code "234") (name "Net-(UF11-QC)") (class "Default")
      (node (ref "RF86") (pin "1") (pinfunction "1_1") (pintype "passive"))
      (node (ref "UF11") (pin "2") (pinfunction "QC_2") (pintype "tri_state"))
    )
    (net (code "235") (name "Net-(UF11-QD)") (class "Default")
      (node (ref "RF85") (pin "1") (pinfunction "1_1") (pintype "passive"))
      (node (ref "UF11") (pin "3") (pinfunction "QD_3") (pintype "tri_state"))
    )
    (net (code "236") (name "Net-(UF11-QE)") (class "Default")
      (node (ref "RF84") (pin "1") (pinfunction "1_1") (pintype "passive"))
      (node (ref "UF11") (pin "4") (pinfunction "QE_4") (pintype "tri_state"))
    )
    (net (code "237") (name "Net-(UF11-QF)") (class "Default")
      (node (ref "RF83") (pin "1") (pinfunction "1_1") (pintype "passive"))
      (node (ref "UF11") (pin "5") (pinfunction "QF_5") (pintype "tri_state"))
    )
    (net (code "238") (name "Net-(UF11-QG)") (class "Default")
      (node (ref "RF82") (pin "1") (pinfunction "1_1") (pintype "passive"))
      (node (ref "UF11") (pin "6") (pinfunction "QG_6") (pintype "tri_state"))
    )
    (net (code "239") (name "Net-(UF11-QH)") (class "Default")
      (node (ref "RF81") (pin "1") (pinfunction "1_1") (pintype "passive"))
      (node (ref "UF11") (pin "7") (pinfunction "QH_7") (pintype "tri_state"))
    )
    (net (code "240") (name "Net-(UF12-QA)") (class "Default")
      (node (ref "RF96") (pin "1") (pinfunction "1_1") (pintype "passive"))
      (node (ref "UF12") (pin "15") (pinfunction "QA_15") (pintype "tri_state"))
    )
    (net (code "241") (name "Net-(UF12-QB)") (class "Default")
      (node (ref "RF95") (pin "1") (pinfunction "1_1") (pintype "passive"))
      (node (ref "UF12") (pin "1") (pinfunction "QB_1") (pintype "tri_state"))
    )
    (net (code "242") (name "Net-(UF12-QC)") (class "Default")
      (node (ref "RF94") (pin "1") (pinfunction "1_1") (pintype "passive"))
      (node (ref "UF12") (pin "2") (pinfunction "QC_2") (pintype "tri_state"))
    )
    (net (code "243") (name "Net-(UF12-QD)") (class "Default")
      (node (ref "RF93") (pin "1") (pinfunction "1_1") (pintype "passive"))
      (node (ref "UF12") (pin "3") (pinfunction "QD_3") (pintype "tri_state"))
    )
    (net (code "244") (name "Net-(UF12-QE)") (class "Default")
      (node (ref "RF92") (pin "1") (pinfunction "1_1") (pintype "passive"))
      (node (ref "UF12") (pin "4") (pinfunction "QE_4") (pintype "tri_state"))
    )
    (net (code "245") (name "Net-(UF12-QF)") (class "Default")
      (node (ref "RF91") (pin "1") (pinfunction "1_1") (pintype "passive"))
      (node (ref "UF12") (pin "5") (pinfunction "QF_5") (pintype "tri_state"))
    )
    (net (code "246") (name "Net-(UF12-QG)") (class "Default")
      (node (ref "RF90") (pin "1") (pinfunction "1_1") (pintype "passive"))
      (node (ref "UF12") (pin "6") (pinfunction "QG_6") (pintype "tri_state"))
    )
    (net (code "247") (name "Net-(UF12-QH)") (class "Default")
      (node (ref "RF89") (pin "1") (pinfunction "1_1") (pintype "passive"))
      (node (ref "UF12") (pin "7") (pinfunction "QH_7") (pintype "tri_state"))
    )
    (net (code "248") (name "Net-(UF13-QA)") (class "Default")
      (node (ref "RF104") (pin "1") (pinfunction "1_1") (pintype "passive"))
      (node (ref "UF13") (pin "15") (pinfunction "QA_15") (pintype "tri_state"))
    )
    (net (code "249") (name "Net-(UF13-QB)") (class "Default")
      (node (ref "RF103") (pin "1") (pinfunction "1_1") (pintype "passive"))
      (node (ref "UF13") (pin "1") (pinfunction "QB_1") (pintype "tri_state"))
    )
    (net (code "250") (name "Net-(UF13-QC)") (class "Default")
      (node (ref "RF102") (pin "1") (pinfunction "1_1") (pintype "passive"))
      (node (ref "UF13") (pin "2") (pinfunction "QC_2") (pintype "tri_state"))
    )
    (net (code "251") (name "Net-(UF13-QD)") (class "Default")
      (node (ref "RF101") (pin "1") (pinfunction "1_1") (pintype "passive"))
      (node (ref "UF13") (pin "3") (pinfunction "QD_3") (pintype "tri_state"))
    )
    (net (code "252") (name "Net-(UF13-QE)") (class "Default")
      (node (ref "RF100") (pin "1") (pinfunction "1_1") (pintype "passive"))
      (node (ref "UF13") (pin "4") (pinfunction "QE_4") (pintype "tri_state"))
    )
    (net (code "253") (name "Net-(UF13-QF)") (class "Default")
      (node (ref "RF99") (pin "1") (pinfunction "1_1") (pintype "passive"))
      (node (ref "UF13") (pin "5") (pinfunction "QF_5") (pintype "tri_state"))
    )
    (net (code "254") (name "Net-(UF13-QG)") (class "Default")
      (node (ref "RF98") (pin "1") (pinfunction "1_1") (pintype "passive"))
      (node (ref "UF13") (pin "6") (pinfunction "QG_6") (pintype "tri_state"))
    )
    (net (code "255") (name "Net-(UF13-QH)") (class "Default")
      (node (ref "RF97") (pin "1") (pinfunction "1_1") (pintype "passive"))
      (node (ref "UF13") (pin "7") (pinfunction "QH_7") (pintype "tri_state"))
    )
    (net (code "256") (name "Net-(UF14-QA)") (class "Default")
      (node (ref "RF112") (pin "1") (pinfunction "1_1") (pintype "passive"))
      (node (ref "UF14") (pin "15") (pinfunction "QA_15") (pintype "tri_state"))
    )
    (net (code "257") (name "Net-(UF14-QB)") (class "Default")
      (node (ref "RF111") (pin "1") (pinfunction "1_1") (pintype "passive"))
      (node (ref "UF14") (pin "1") (pinfunction "QB_1") (pintype "tri_state"))
    )
    (net (code "258") (name "Net-(UF14-QC)") (class "Default")
      (node (ref "RF110") (pin "1") (pinfunction "1_1") (pintype "passive"))
      (node (ref "UF14") (pin "2") (pinfunction "QC_2") (pintype "tri_state"))
    )
    (net (code "259") (name "Net-(UF14-QD)") (class "Default")
      (node (ref "RF109") (pin "1") (pinfunction "1_1") (pintype "passive"))
      (node (ref "UF14") (pin "3") (pinfunction "QD_3") (pintype "tri_state"))
    )
    (net (code "260") (name "Net-(UF14-QE)") (class "Default")
      (node (ref "RF108") (pin "1") (pinfunction "1_1") (pintype "passive"))
      (node (ref "UF14") (pin "4") (pinfunction "QE_4") (pintype "tri_state"))
    )
    (net (code "261") (name "Net-(UF14-QF)") (class "Default")
      (node (ref "RF107") (pin "1") (pinfunction "1_1") (pintype "passive"))
      (node (ref "UF14") (pin "5") (pinfunction "QF_5") (pintype "tri_state"))
    )
    (net (code "262") (name "Net-(UF14-QG)") (class "Default")
      (node (ref "RF106") (pin "1") (pinfunction "1_1") (pintype "passive"))
      (node (ref "UF14") (pin "6") (pinfunction "QG_6") (pintype "tri_state"))
    )
    (net (code "263") (name "Net-(UF14-QH)") (class "Default")
      (node (ref "RF105") (pin "1") (pinfunction "1_1") (pintype "passive"))
      (node (ref "UF14") (pin "7") (pinfunction "QH_7") (pintype "tri_state"))
    )
    (net (code "264") (name "Net-(UF15-QA)") (class "Default")
      (node (ref "RF120") (pin "1") (pinfunction "1_1") (pintype "passive"))
      (node (ref "UF15") (pin "15") (pinfunction "QA_15") (pintype "tri_state"))
    )
    (net (code "265") (name "Net-(UF15-QB)") (class "Default")
      (node (ref "RF119") (pin "1") (pinfunction "1_1") (pintype "passive"))
      (node (ref "UF15") (pin "1") (pinfunction "QB_1") (pintype "tri_state"))
    )
    (net (code "266") (name "Net-(UF15-QC)") (class "Default")
      (node (ref "RF118") (pin "1") (pinfunction "1_1") (pintype "passive"))
      (node (ref "UF15") (pin "2") (pinfunction "QC_2") (pintype "tri_state"))
    )
    (net (code "267") (name "Net-(UF15-QD)") (class "Default")
      (node (ref "RF117") (pin "1") (pinfunction "1_1") (pintype "passive"))
      (node (ref "UF15") (pin "3") (pinfunction "QD_3") (pintype "tri_state"))
    )
    (net (code "268") (name "Net-(UF15-QE)") (class "Default")
      (node (ref "RF116") (pin "1") (pinfunction "1_1") (pintype "passive"))
      (node (ref "UF15") (pin "4") (pinfunction "QE_4") (pintype "tri_state"))
    )
    (net (code "269") (name "Net-(UF15-QF)") (class "Default")
      (node (ref "RF115") (pin "1") (pinfunction "1_1") (pintype "passive"))
      (node (ref "UF15") (pin "5") (pinfunction "QF_5") (pintype "tri_state"))
    )
    (net (code "270") (name "Net-(UF15-QG)") (class "Default")
      (node (ref "RF114") (pin "1") (pinfunction "1_1") (pintype "passive"))
      (node (ref "UF15") (pin "6") (pinfunction "QG_6") (pintype "tri_state"))
    )
    (net (code "271") (name "Net-(UF15-QH)") (class "Default")
      (node (ref "RF113") (pin "1") (pinfunction "1_1") (pintype "passive"))
      (node (ref "UF15") (pin "7") (pinfunction "QH_7") (pintype "tri_state"))
    )
    (net (code "272") (name "Net-(UF16-QA)") (class "Default")
      (node (ref "RF128") (pin "1") (pinfunction "1_1") (pintype "passive"))
      (node (ref "UF16") (pin "15") (pinfunction "QA_15") (pintype "tri_state"))
    )
    (net (code "273") (name "Net-(UF16-QB)") (class "Default")
      (node (ref "RF127") (pin "1") (pinfunction "1_1") (pintype "passive"))
      (node (ref "UF16") (pin "1") (pinfunction "QB_1") (pintype "tri_state"))
    )
    (net (code "274") (name "Net-(UF16-QC)") (class "Default")
      (node (ref "RF126") (pin "1") (pinfunction "1_1") (pintype "passive"))
      (node (ref "UF16") (pin "2") (pinfunction "QC_2") (pintype "tri_state"))
    )
    (net (code "275") (name "Net-(UF16-QD)") (class "Default")
      (node (ref "RF125") (pin "1") (pinfunction "1_1") (pintype "passive"))
      (node (ref "UF16") (pin "3") (pinfunction "QD_3") (pintype "tri_state"))
    )
    (net (code "276") (name "Net-(UF16-QE)") (class "Default")
      (node (ref "RF124") (pin "1") (pinfunction "1_1") (pintype "passive"))
      (node (ref "UF16") (pin "4") (pinfunction "QE_4") (pintype "tri_state"))
    )
    (net (code "277") (name "Net-(UF16-QF)") (class "Default")
      (node (ref "RF123") (pin "1") (pinfunction "1_1") (pintype "passive"))
      (node (ref "UF16") (pin "5") (pinfunction "QF_5") (pintype "tri_state"))
    )
    (net (code "278") (name "Net-(UF16-QG)") (class "Default")
      (node (ref "RF122") (pin "1") (pinfunction "1_1") (pintype "passive"))
      (node (ref "UF16") (pin "6") (pinfunction "QG_6") (pintype "tri_state"))
    )
    (net (code "279") (name "Net-(UF16-QH)") (class "Default")
      (node (ref "RF121") (pin "1") (pinfunction "1_1") (pintype "passive"))
      (node (ref "UF16") (pin "7") (pinfunction "QH_7") (pintype "tri_state"))
    )
    (net (code "280") (name "unconnected-(UF1-SDO-Pad9)") (class "Default")
      (node (ref "UF1") (pin "9") (pinfunction "SDO_9") (pintype "output+no_connect"))
    )
  )
)
